# task_eagle.net
KiCad netlist of a schematic drawn in EAGLE
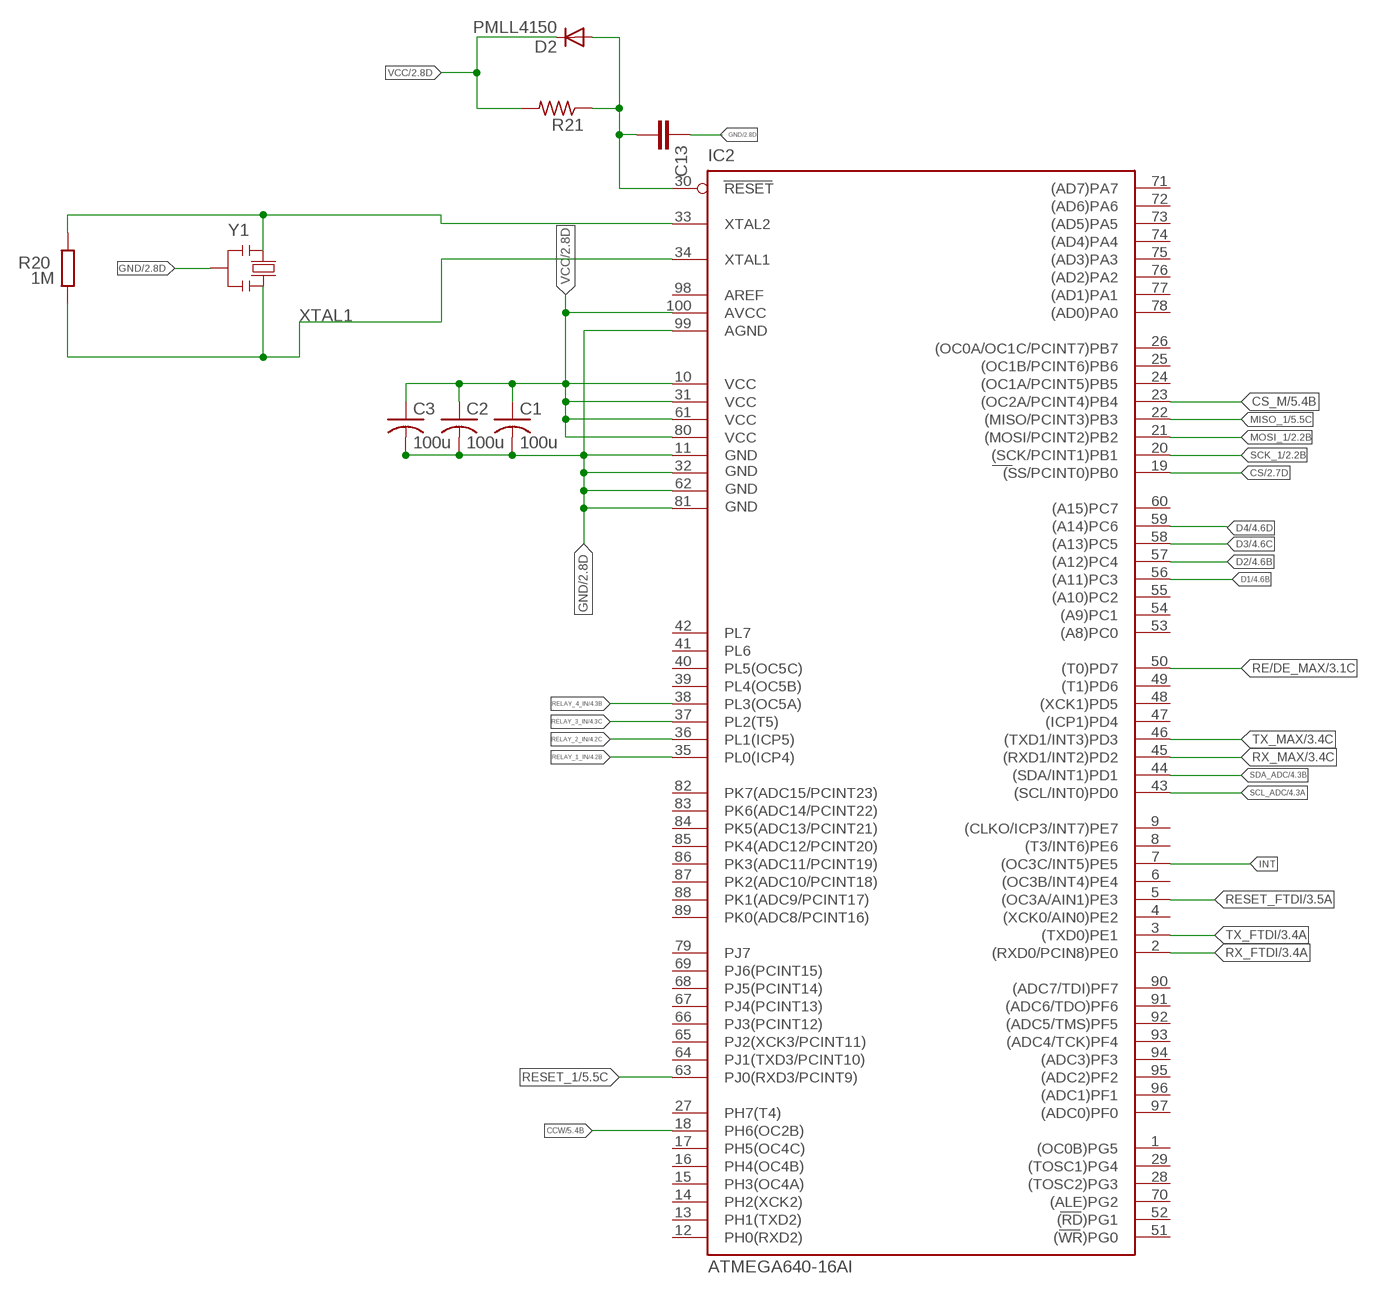
[diagram p0: schematic, sheet 1]
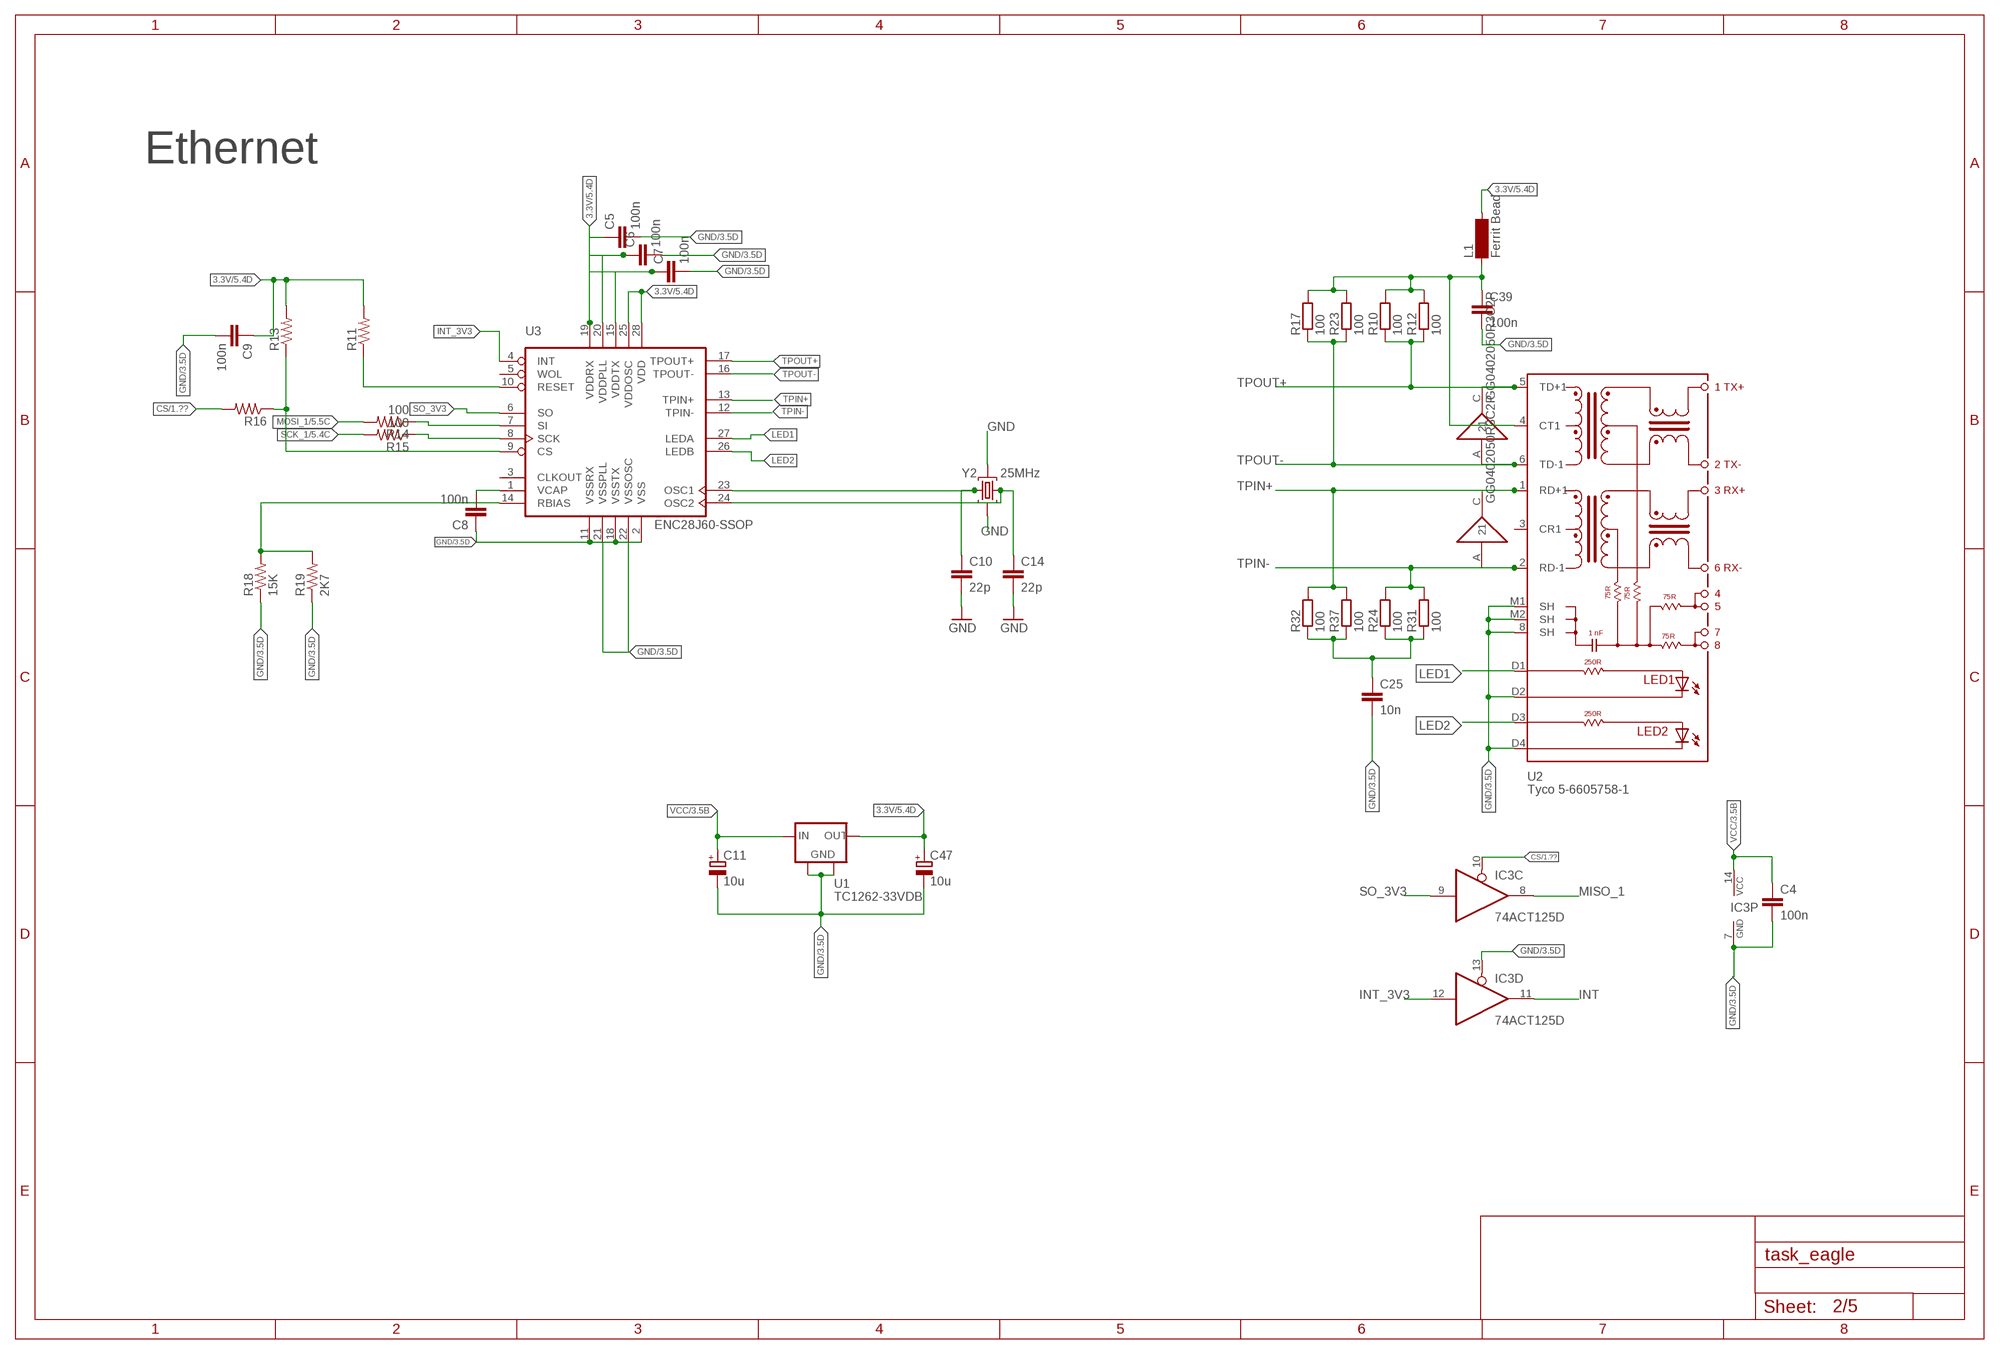
[diagram p1: schematic, sheet 2]
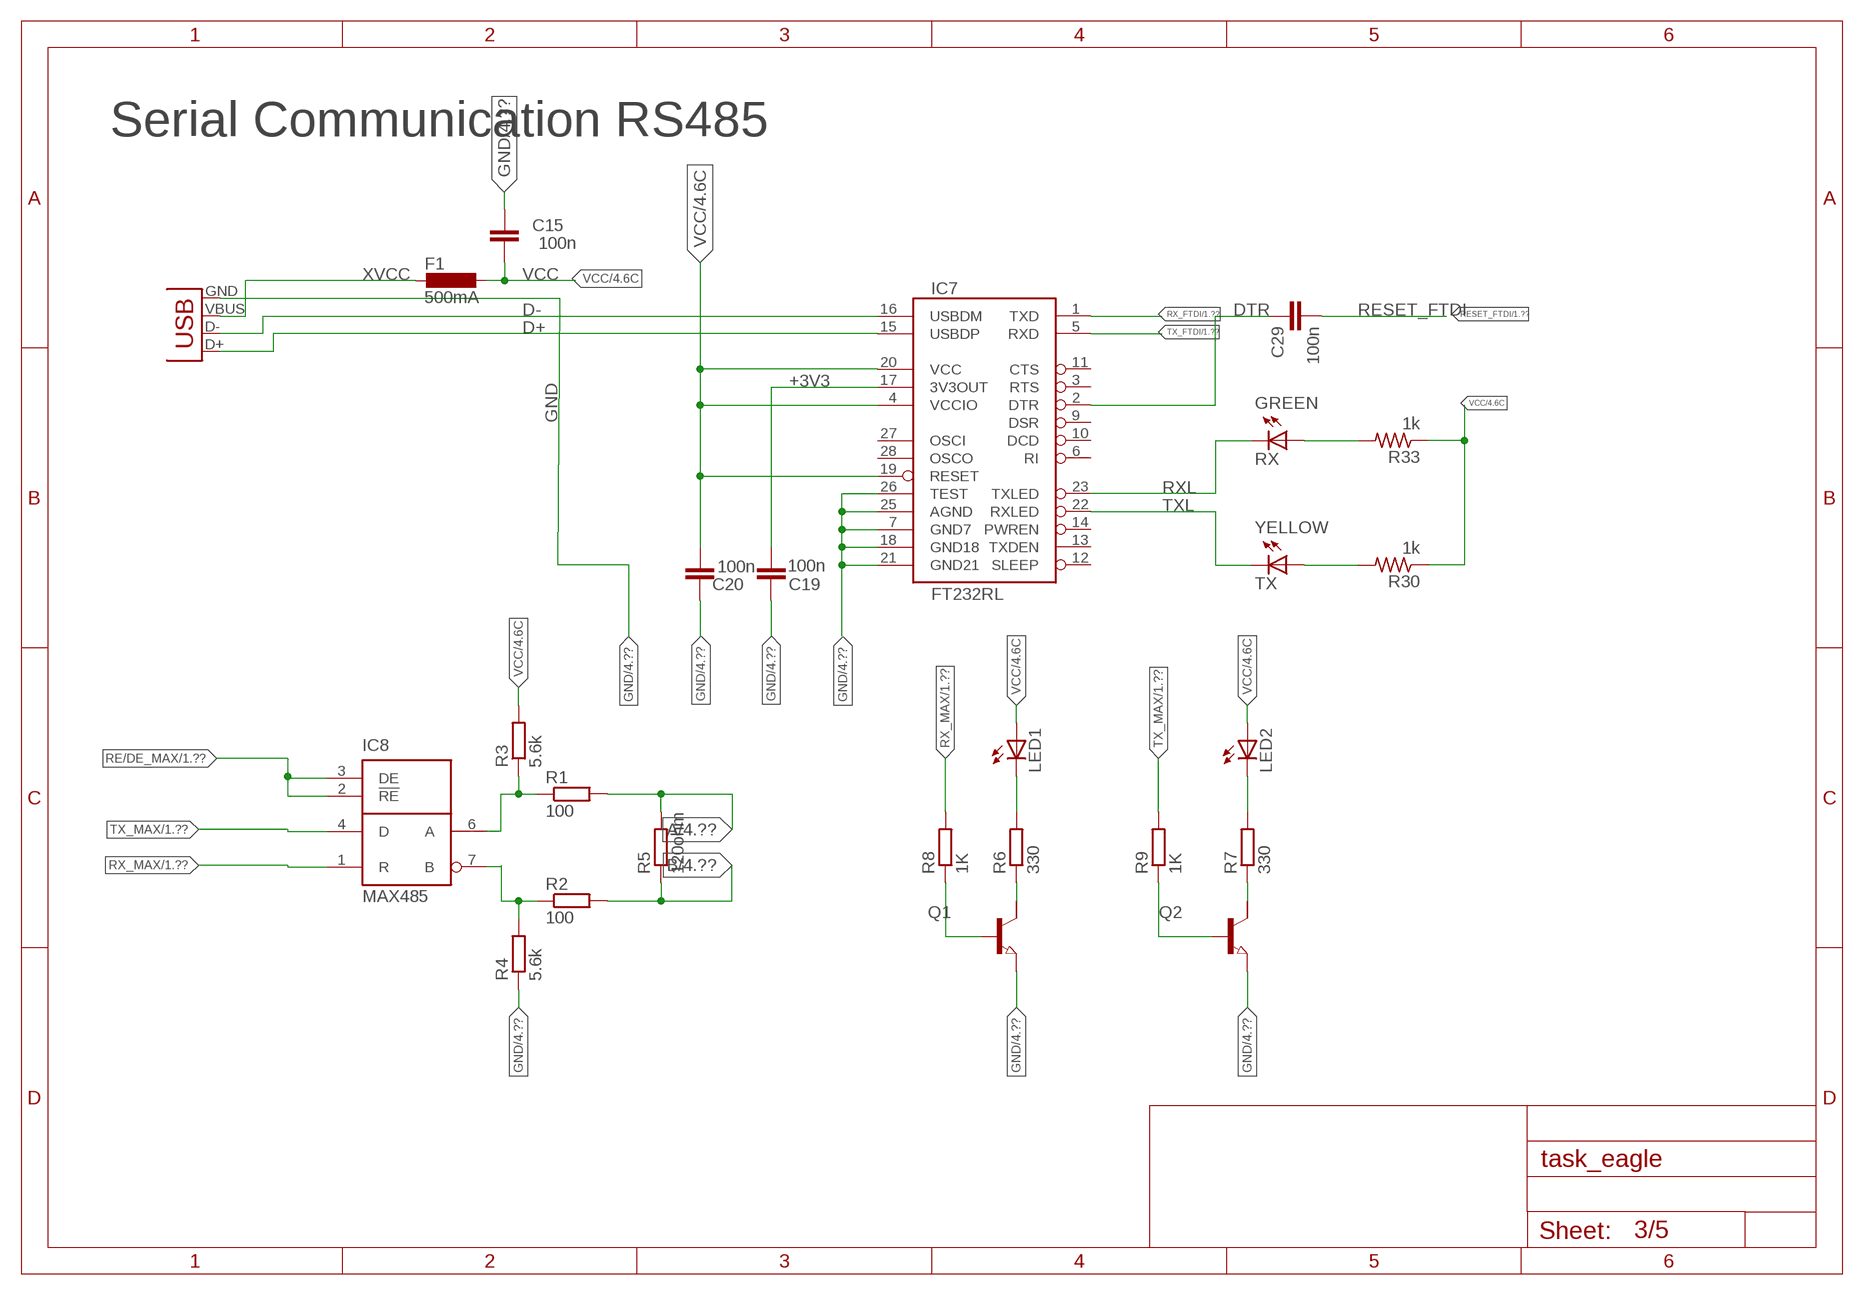
[diagram p2: schematic, sheet 3]
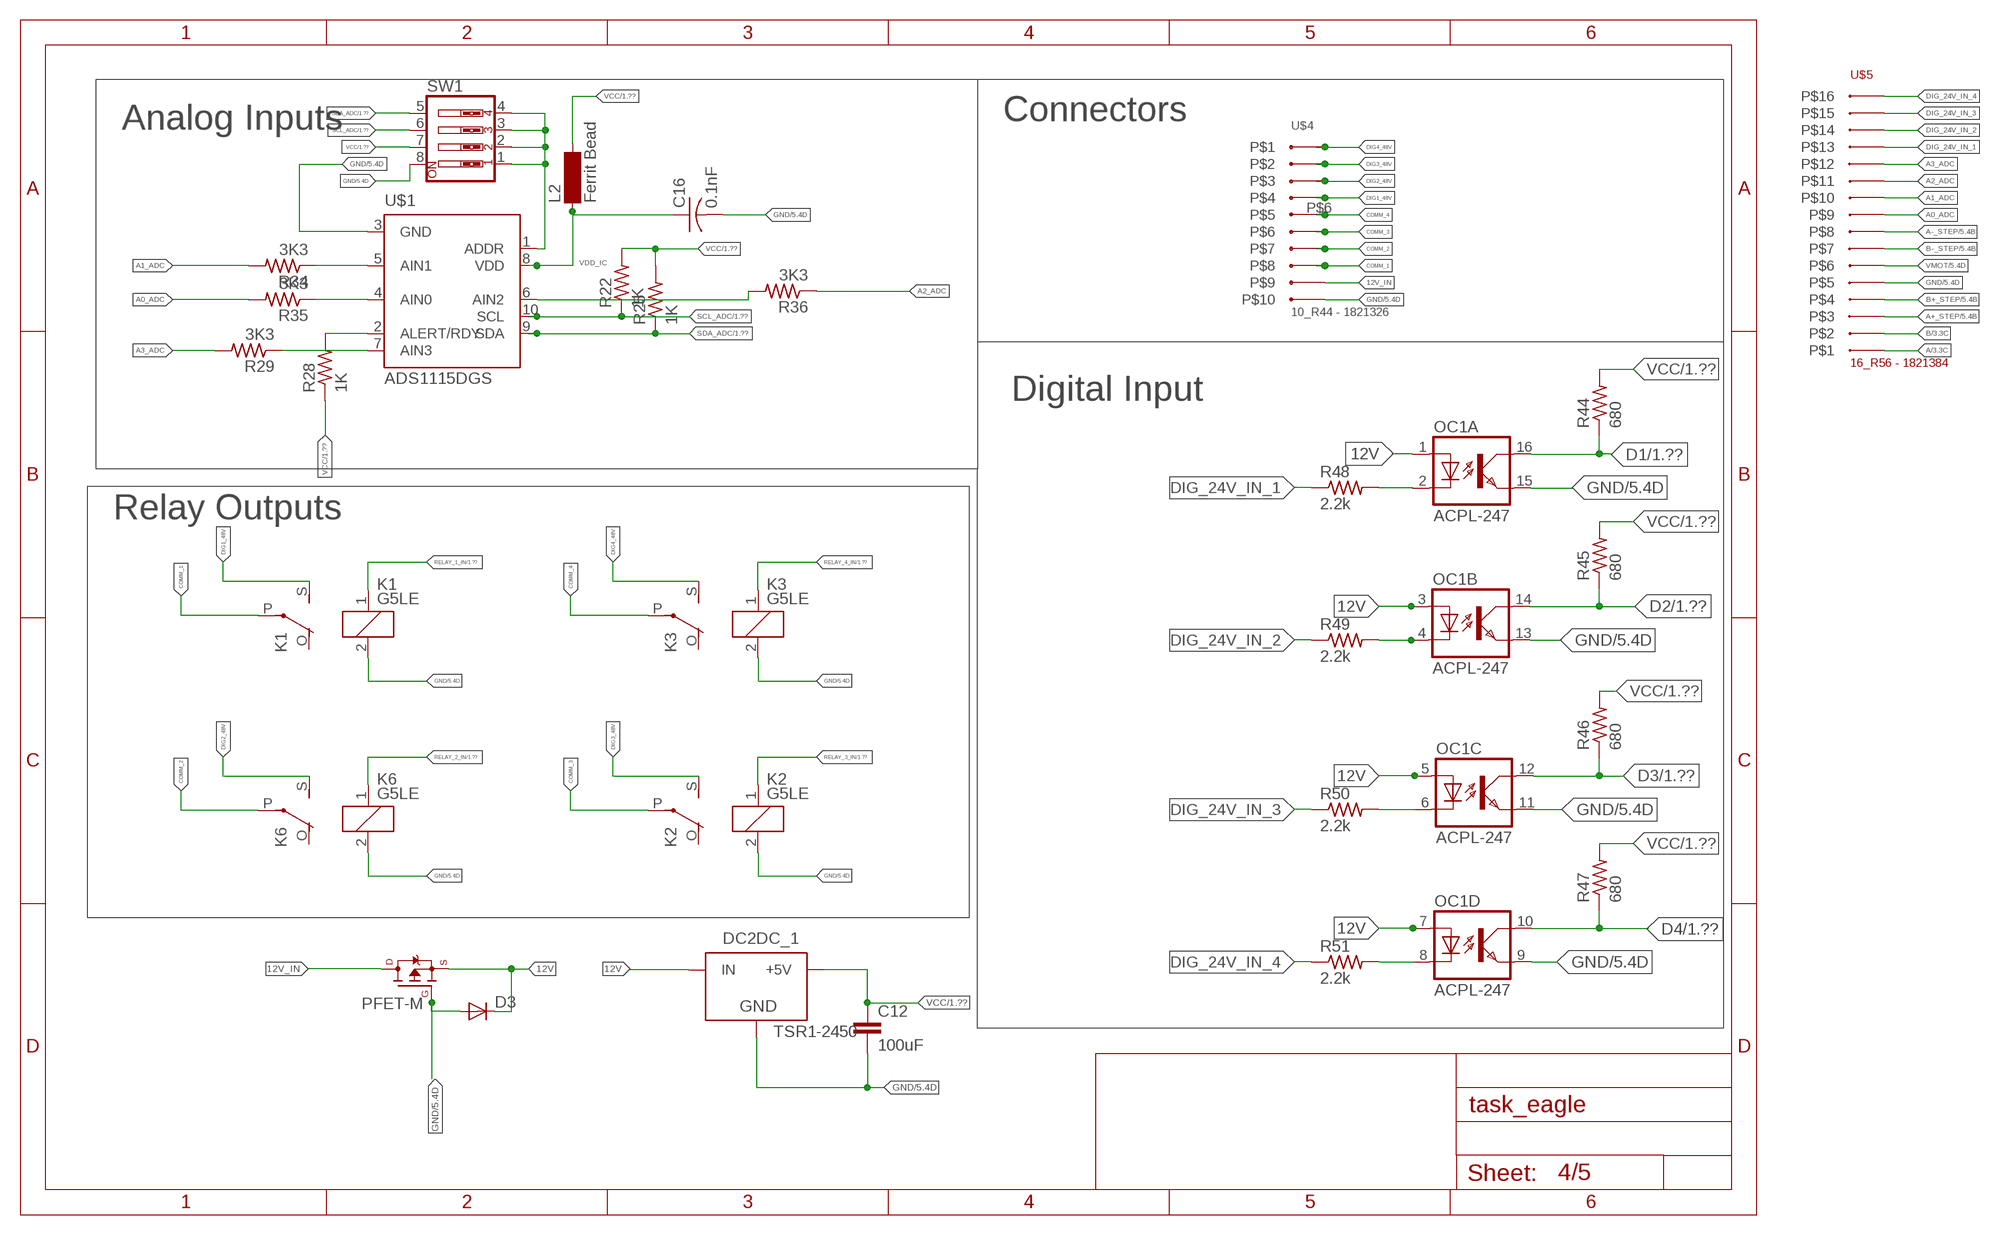
[diagram p3: schematic, sheet 4]
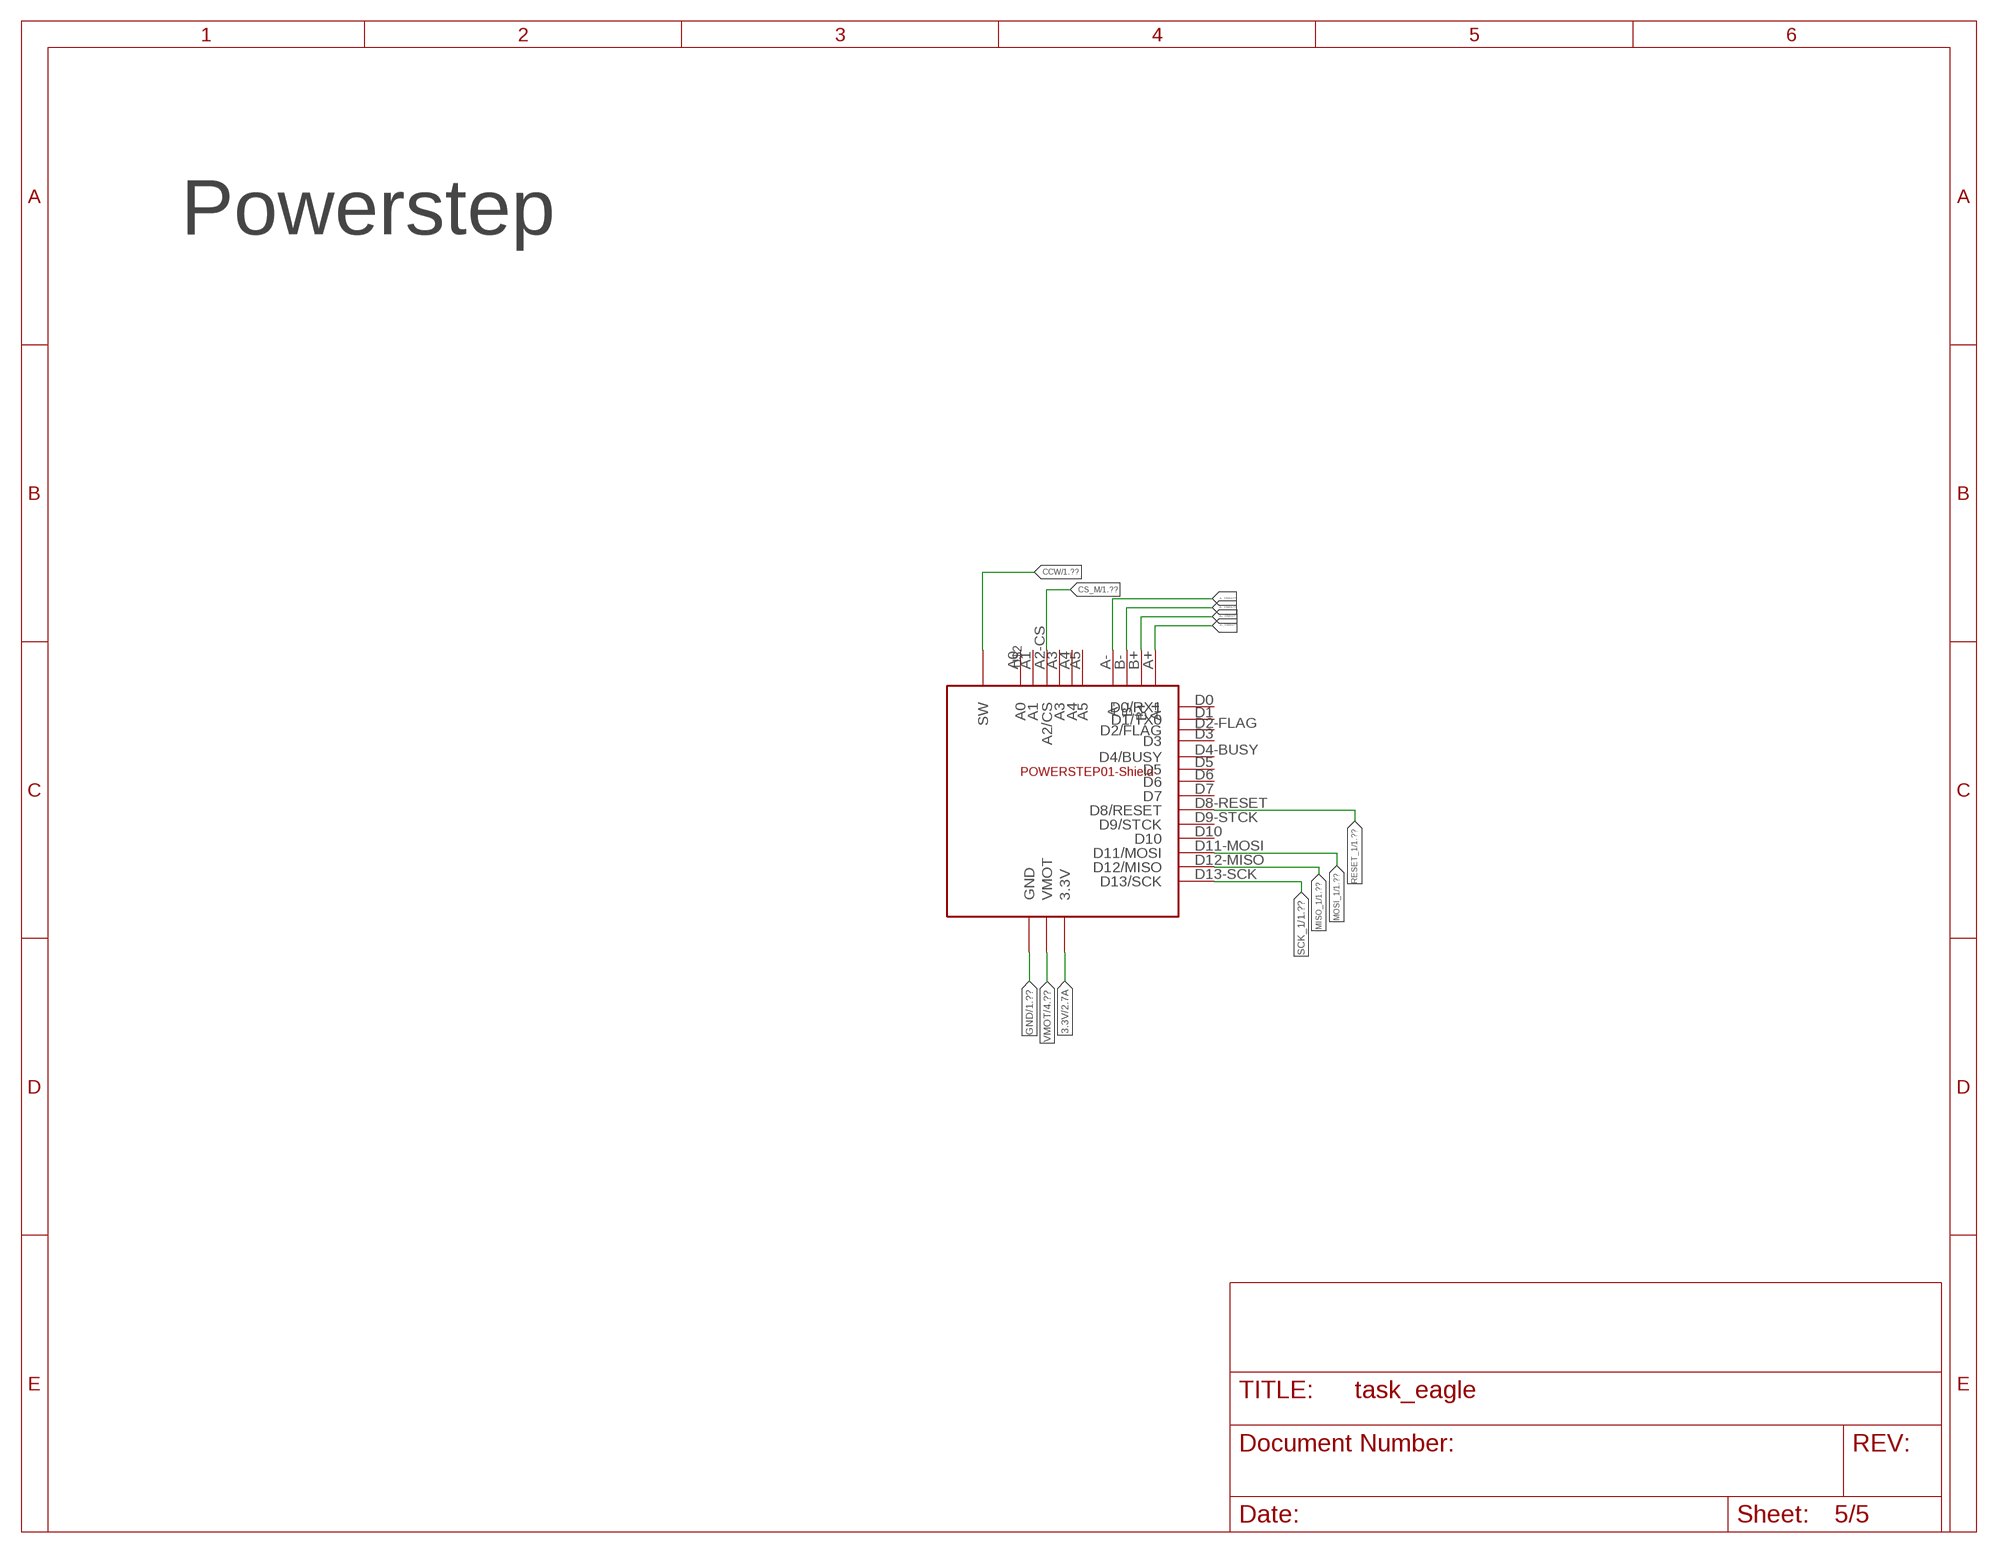
[diagram p4: schematic, sheet 5]

(export (version "E")
  (design (tool "Eeschema 10.0.6"))
  (components
    (comp (ref "C4")
      (value "100n")
      (footprint "eagle-import:C0603")
      (libsource (lib "eagle-import") (part "rcl_C-EUC0603"))
    )
    (comp (ref "C5")
      (value "100n")
      (footprint "eagle-import:C0603")
      (libsource (lib "eagle-import") (part "rcl_C-EUC0603"))
    )
    (comp (ref "C6")
      (value "100n")
      (footprint "eagle-import:C0603")
      (libsource (lib "eagle-import") (part "rcl_C-EUC0603"))
    )
    (comp (ref "C7")
      (value "100n")
      (footprint "eagle-import:C0603")
      (libsource (lib "eagle-import") (part "rcl_C-EUC0603"))
    )
    (comp (ref "C8")
      (value "100n")
      (footprint "eagle-import:C0603")
      (libsource (lib "eagle-import") (part "rcl_C-EUC0603"))
    )
    (comp (ref "C9")
      (value "100n")
      (footprint "eagle-import:C0603")
      (libsource (lib "eagle-import") (part "rcl_C-EUC0603"))
    )
    (comp (ref "C10")
      (value "22p")
      (footprint "eagle-import:C0603")
      (libsource (lib "eagle-import") (part "rcl_C-EUC0603"))
    )
    (comp (ref "C11")
      (value "10u")
      (footprint "eagle-import:153CLV-0605")
      (libsource (lib "eagle-import") (part "CPOL-EU153CLV-0605"))
    )
    (comp (ref "C14")
      (value "22p")
      (footprint "eagle-import:C0603")
      (libsource (lib "eagle-import") (part "rcl_C-EUC0603"))
    )
    (comp (ref "C25")
      (value "10n")
      (footprint "eagle-import:C0603")
      (libsource (lib "eagle-import") (part "rcl_C-EUC0603"))
    )
    (comp (ref "C39")
      (value "100n")
      (footprint "eagle-import:C0603")
      (libsource (lib "eagle-import") (part "rcl_C-EUC0603"))
    )
    (comp (ref "C47")
      (value "10u")
      (footprint "eagle-import:153CLV-0605")
      (libsource (lib "eagle-import") (part "CPOL-EU153CLV-0605"))
    )
    (comp (ref "IC3")
      (value "74ACT125D")
      (footprint "eagle-import:SO14")
      (libsource (lib "eagle-import") (part "74125DACT"))
    )
    (comp (ref "L1")
      (value "Ferrit Bead")
      (footprint "eagle-import:SM-1206")
      (libsource (lib "eagle-import") (part "SM-1206"))
    )
    (comp (ref "R10")
      (value "100")
      (footprint "eagle-import:R0603")
      (libsource (lib "eagle-import") (part "rcl_R-EU_R0603"))
    )
    (comp (ref "R11")
      (value "R-US_R0603")
      (footprint "eagle-import:R0603")
      (libsource (lib "eagle-import") (part "R-US_R0603"))
    )
    (comp (ref "R12")
      (value "100")
      (footprint "eagle-import:R0603")
      (libsource (lib "eagle-import") (part "rcl_R-EU_R0603"))
    )
    (comp (ref "R13")
      (value "R-US_R0603")
      (footprint "eagle-import:R0603")
      (libsource (lib "eagle-import") (part "R-US_R0603"))
    )
    (comp (ref "R14")
      (value "100")
      (footprint "eagle-import:R0603")
      (libsource (lib "eagle-import") (part "R-US_R0603"))
    )
    (comp (ref "R15")
      (value "100")
      (footprint "eagle-import:R0603")
      (libsource (lib "eagle-import") (part "R-US_R0603"))
    )
    (comp (ref "R16")
      (value "R-US_R0603")
      (footprint "eagle-import:R0603")
      (libsource (lib "eagle-import") (part "R-US_R0603"))
    )
    (comp (ref "R17")
      (value "100")
      (footprint "eagle-import:R0603")
      (libsource (lib "eagle-import") (part "rcl_R-EU_R0603"))
    )
    (comp (ref "R18")
      (value "15K")
      (footprint "eagle-import:R0603")
      (libsource (lib "eagle-import") (part "R-US_R0603"))
    )
    (comp (ref "R19")
      (value "2K7")
      (footprint "eagle-import:R0603")
      (libsource (lib "eagle-import") (part "R-US_R0603"))
    )
    (comp (ref "R23")
      (value "100")
      (footprint "eagle-import:R0603")
      (libsource (lib "eagle-import") (part "rcl_R-EU_R0603"))
    )
    (comp (ref "R24")
      (value "100")
      (footprint "eagle-import:R0603")
      (libsource (lib "eagle-import") (part "rcl_R-EU_R0603"))
    )
    (comp (ref "R31")
      (value "100")
      (footprint "eagle-import:R0603")
      (libsource (lib "eagle-import") (part "rcl_R-EU_R0603"))
    )
    (comp (ref "R32")
      (value "100")
      (footprint "eagle-import:R0603")
      (libsource (lib "eagle-import") (part "rcl_R-EU_R0603"))
    )
    (comp (ref "R37")
      (value "100")
      (footprint "eagle-import:R0603")
      (libsource (lib "eagle-import") (part "rcl_R-EU_R0603"))
    )
    (comp (ref "U$6")
      (value "GG0402050R3C2P")
      (footprint "eagle-import:0402")
      (libsource (lib "eagle-import") (part "GG0402050R3C2P"))
    )
    (comp (ref "U$7")
      (value "GG0402050R3C2P")
      (footprint "eagle-import:0402")
      (libsource (lib "eagle-import") (part "GG0402050R3C2P"))
    )
    (comp (ref "U1")
      (value "TC1262-33VDB")
      (footprint "eagle-import:SOT223")
      (libsource (lib "eagle-import") (part "TC1262-50VDB"))
    )
    (comp (ref "U2")
      (value "Tyco 5-6605758-1")
      (footprint "eagle-import:5-6605758-1")
      (libsource (lib "eagle-import") (part "5-6605758-1"))
    )
    (comp (ref "U3")
      (value "ENC28J60-SSOP")
      (footprint "eagle-import:SSOP28")
      (libsource (lib "eagle-import") (part "ENC28J60-SSOP"))
    )
    (comp (ref "Y2")
      (value "25MHz")
      (footprint "eagle-import:CRYSTAL-3.2-2.5")
      (libsource (lib "eagle-import") (part "CRYSTAL-3.2-2.5"))
    )
    (comp (ref "U$2")
      (value "POWERSTEP01-SHIELD")
      (footprint "eagle-import:POWERSTEP1")
      (libsource (lib "eagle-import") (part "POWERSTEP01-SHIELD"))
    )
    (comp (ref "C12")
      (value "100uF")
      (footprint "eagle-import:C0603")
      (libsource (lib "eagle-import") (part "CC0603"))
    )
    (comp (ref "C16")
      (value "0.1nF")
      (footprint "eagle-import:C0603")
      (libsource (lib "eagle-import") (part "C-USC0603"))
    )
    (comp (ref "D3")
      (value "DIODE-MINIMELF")
      (footprint "eagle-import:MINIMELF")
      (libsource (lib "eagle-import") (part "DIODE-MINIMELF"))
    )
    (comp (ref "DC2DC_1")
      (value "TSR1-2450")
      (footprint "eagle-import:TSR-1")
      (libsource (lib "eagle-import") (part "TSR1-2450"))
    )
    (comp (ref "K1")
      (value "G5LE")
      (footprint "eagle-import:G5LE")
      (libsource (lib "eagle-import") (part "G5LE"))
    )
    (comp (ref "K2")
      (value "G5LE")
      (footprint "eagle-import:G5LE")
      (libsource (lib "eagle-import") (part "G5LE"))
    )
    (comp (ref "K3")
      (value "G5LE")
      (footprint "eagle-import:G5LE")
      (libsource (lib "eagle-import") (part "G5LE"))
    )
    (comp (ref "K6")
      (value "G5LE")
      (footprint "eagle-import:G5LE")
      (libsource (lib "eagle-import") (part "G5LE"))
    )
    (comp (ref "L2")
      (value "Ferrit Bead")
      (footprint "eagle-import:SM-1206")
      (libsource (lib "eagle-import") (part "SM-1206"))
    )
    (comp (ref "OC1")
      (value "ACPL-247")
      (footprint "eagle-import:SOP16")
      (libsource (lib "eagle-import") (part "ACPL-247"))
    )
    (comp (ref "PFET-M")
      (value "FQP47P06NORMAL")
      (footprint "eagle-import:FQP47P06-NORMAL")
      (libsource (lib "eagle-import") (part "FQP47P06NORMAL"))
    )
    (comp (ref "R22")
      (value "1K")
      (footprint "eagle-import:R0603")
      (libsource (lib "eagle-import") (part "resistor_R-US_R0603"))
    )
    (comp (ref "R25")
      (value "1K")
      (footprint "eagle-import:R0603")
      (libsource (lib "eagle-import") (part "resistor_R-US_R0603"))
    )
    (comp (ref "R28")
      (value "1K")
      (footprint "eagle-import:R0603")
      (libsource (lib "eagle-import") (part "resistor_R-US_R0603"))
    )
    (comp (ref "R29")
      (value "3K3")
      (footprint "eagle-import:R0603")
      (libsource (lib "eagle-import") (part "resistor_R-US_R0603"))
    )
    (comp (ref "R34")
      (value "3K3")
      (footprint "eagle-import:R0603")
      (libsource (lib "eagle-import") (part "resistor_R-US_R0603"))
    )
    (comp (ref "R35")
      (value "3K3")
      (footprint "eagle-import:R0603")
      (libsource (lib "eagle-import") (part "resistor_R-US_R0603"))
    )
    (comp (ref "R36")
      (value "3K3")
      (footprint "eagle-import:R0603")
      (libsource (lib "eagle-import") (part "resistor_R-US_R0603"))
    )
    (comp (ref "R44")
      (value "680")
      (footprint "eagle-import:R0603")
      (libsource (lib "eagle-import") (part "R-US_R0603"))
    )
    (comp (ref "R45")
      (value "680")
      (footprint "eagle-import:R0603")
      (libsource (lib "eagle-import") (part "R-US_R0603"))
    )
    (comp (ref "R46")
      (value "680")
      (footprint "eagle-import:R0603")
      (libsource (lib "eagle-import") (part "R-US_R0603"))
    )
    (comp (ref "R47")
      (value "680")
      (footprint "eagle-import:R0603")
      (libsource (lib "eagle-import") (part "R-US_R0603"))
    )
    (comp (ref "R48")
      (value "2.2k")
      (footprint "eagle-import:R0603")
      (libsource (lib "eagle-import") (part "R-US_R0603"))
    )
    (comp (ref "R49")
      (value "2.2k")
      (footprint "eagle-import:R0603")
      (libsource (lib "eagle-import") (part "R-US_R0603"))
    )
    (comp (ref "R50")
      (value "2.2k")
      (footprint "eagle-import:R0603")
      (libsource (lib "eagle-import") (part "R-US_R0603"))
    )
    (comp (ref "R51")
      (value "2.2k")
      (footprint "eagle-import:R0603")
      (libsource (lib "eagle-import") (part "R-US_R0603"))
    )
    (comp (ref "SW1")
      (value "SW_DIP-4")
      (footprint "eagle-import:EDG-04")
      (libsource (lib "eagle-import") (part "SW_DIP-4"))
    )
    (comp (ref "U$1")
      (value "ADS1115DGS")
      (footprint "eagle-import:MSOP10")
      (libsource (lib "eagle-import") (part "ADS1115DGS"))
    )
    (comp (ref "U$4")
      (value "10_R44 - 1821326")
      (footprint "eagle-import:10_R44 - 1821326")
      (libsource (lib "eagle-import") (part "10_R44 - 1821326"))
    )
    (comp (ref "U$5")
      (value "16_R56 - 1821384")
      (footprint "eagle-import:16_R56 - 1821384")
      (libsource (lib "eagle-import") (part "16_R56 - 1821384"))
    )
    (comp (ref "C15")
      (value "100n")
      (footprint "eagle-import:C0603")
      (libsource (lib "eagle-import") (part "rcl_C-EUC0603"))
    )
    (comp (ref "C19")
      (value "100n")
      (footprint "eagle-import:C0603-ROUND")
      (libsource (lib "eagle-import") (part "C-EU0603-RND"))
    )
    (comp (ref "C20")
      (value "100n")
      (footprint "eagle-import:C0603-ROUND")
      (libsource (lib "eagle-import") (part "C-EU0603-RND"))
    )
    (comp (ref "C29")
      (value "100n")
      (footprint "eagle-import:C0603-ROUND")
      (libsource (lib "eagle-import") (part "C-EU0603-RND"))
    )
    (comp (ref "F1")
      (value "500mA")
      (footprint "eagle-import:L1812")
      (libsource (lib "eagle-import") (part "L-EUL1812"))
    )
    (comp (ref "IC7")
      (value "FT232RL")
      (footprint "eagle-import:SSOP28DB")
      (libsource (lib "eagle-import") (part "FT232RLSSOP"))
    )
    (comp (ref "IC8")
      (value "MAX485")
      (footprint "eagle-import:SO-08")
      (fields (field (name "MF") "TEXAS INSTRUMENTS") (field (name "MPN") "SN75ALS176AD"))
      (libsource (lib "eagle-import") (part "75ALS176DA"))
    )
    (comp (ref "LED1")
      (value "LED_ESML0603")
      (footprint "eagle-import:LED_SML0603")
      (libsource (lib "eagle-import") (part "LED_ESML0603"))
    )
    (comp (ref "LED2")
      (value "LED_ESML0603")
      (footprint "eagle-import:LED_SML0603")
      (libsource (lib "eagle-import") (part "LED_ESML0603"))
    )
    (comp (ref "Q1")
      (value "NPN-TRANSISTIOR-2COLSOT89")
      (footprint "eagle-import:SOT89")
      (libsource (lib "eagle-import") (part "NPN-TRANSISTIOR-2COLSOT89"))
    )
    (comp (ref "Q2")
      (value "NPN-TRANSISTIOR-2COLSOT89")
      (footprint "eagle-import:SOT89")
      (libsource (lib "eagle-import") (part "NPN-TRANSISTIOR-2COLSOT89"))
    )
    (comp (ref "R1")
      (value "100")
      (footprint "eagle-import:R0603")
      (libsource (lib "eagle-import") (part "RR0603"))
    )
    (comp (ref "R2")
      (value "100")
      (footprint "eagle-import:R0603")
      (libsource (lib "eagle-import") (part "RR0603"))
    )
    (comp (ref "R3")
      (value "5.6k")
      (footprint "eagle-import:R0603")
      (libsource (lib "eagle-import") (part "RR0603"))
    )
    (comp (ref "R4")
      (value "5.6k")
      (footprint "eagle-import:R0603")
      (libsource (lib "eagle-import") (part "RR0603"))
    )
    (comp (ref "R5")
      (value "120ohm")
      (footprint "eagle-import:R0603")
      (libsource (lib "eagle-import") (part "RR0603"))
    )
    (comp (ref "R6")
      (value "330")
      (footprint "eagle-import:R0603")
      (libsource (lib "eagle-import") (part "RR0603"))
    )
    (comp (ref "R7")
      (value "330")
      (footprint "eagle-import:R0603")
      (libsource (lib "eagle-import") (part "RR0603"))
    )
    (comp (ref "R8")
      (value "1K")
      (footprint "eagle-import:R0603")
      (libsource (lib "eagle-import") (part "RR0603"))
    )
    (comp (ref "R9")
      (value "1K")
      (footprint "eagle-import:R0603")
      (libsource (lib "eagle-import") (part "RR0603"))
    )
    (comp (ref "R30")
      (value "1k")
      (footprint "eagle-import:R0603")
      (libsource (lib "eagle-import") (part "resistor_R-US_R0603"))
    )
    (comp (ref "R33")
      (value "1k")
      (footprint "eagle-import:R0603")
      (libsource (lib "eagle-import") (part "resistor_R-US_R0603"))
    )
    (comp (ref "RX")
      (value "GREEN")
      (footprint "eagle-import:CHIPLED_0603")
      (libsource (lib "eagle-import") (part "LEDCHIPLED_0603"))
    )
    (comp (ref "TX")
      (value "YELLOW")
      (footprint "eagle-import:CHIPLED_0603")
      (libsource (lib "eagle-import") (part "LEDCHIPLED_0603"))
    )
    (comp (ref "USB")
      (value "USB")
      (footprint "eagle-import:USB-B-PTH-VERTICAL")
      (libsource (lib "eagle-import") (part "USBPTH-VERTICAL"))
    )
    (comp (ref "C1")
      (value "100u")
      (footprint "eagle-import:C0603")
      (libsource (lib "eagle-import") (part "C-USC0603"))
    )
    (comp (ref "C2")
      (value "100u")
      (footprint "eagle-import:C0603")
      (libsource (lib "eagle-import") (part "C-USC0603"))
    )
    (comp (ref "C3")
      (value "100u")
      (footprint "eagle-import:C0603")
      (libsource (lib "eagle-import") (part "C-USC0603"))
    )
    (comp (ref "C13")
      (value "CC0603")
      (footprint "eagle-import:C0603")
      (libsource (lib "eagle-import") (part "CC0603"))
    )
    (comp (ref "D2")
      (value "PMLL4150")
      (footprint "eagle-import:SOD80C")
      (libsource (lib "eagle-import") (part "PMLL4150"))
    )
    (comp (ref "IC2")
      (value "ATMEGA640-16AI")
      (footprint "eagle-import:TQFP100")
      (libsource (lib "eagle-import") (part "ATMEGAAI640-16"))
    )
    (comp (ref "R20")
      (value "1M")
      (footprint "eagle-import:R0603-ROUND")
      (libsource (lib "eagle-import") (part "R-EU_R0603"))
    )
    (comp (ref "R21")
      (value "R-US_R0603")
      (footprint "eagle-import:R0603")
      (libsource (lib "eagle-import") (part "resistor_R-US_R0603"))
    )
    (comp (ref "Y1")
      (value "RESONATORMU")
      (footprint "eagle-import:RESONATOR")
      (libsource (lib "eagle-import") (part "RESONATORMU"))
    )
  )
  (nets
    (net (code "1") (name "+3V3") (class "Default")
      (node (ref "C19") (pin "2") (pinfunction "2_2") (pintype "passive"))
      (node (ref "IC7") (pin "17") (pinfunction "3V3OUT_17") (pintype "output"))
    )
    (net (code "2") (name "3.3V") (class "Default")
      (node (ref "C47") (pin "+") (pinfunction "+_+") (pintype "passive"))
      (node (ref "C5") (pin "1") (pinfunction "1_1") (pintype "passive"))
      (node (ref "C6") (pin "1") (pinfunction "1_1") (pintype "passive"))
      (node (ref "C7") (pin "1") (pinfunction "1_1") (pintype "passive"))
      (node (ref "C9") (pin "1") (pinfunction "1_1") (pintype "passive"))
      (node (ref "L1") (pin "2") (pinfunction "2_2") (pintype "passive"))
      (node (ref "R11") (pin "2") (pinfunction "2_2") (pintype "passive"))
      (node (ref "R13") (pin "2") (pinfunction "2_2") (pintype "passive"))
      (node (ref "U$2") (pin "3.3V") (pinfunction "3.3V_3.3V") (pintype "power_in"))
      (node (ref "U$2") (pin "IOREF") (pinfunction "3.3V_IOREF") (pintype "power_in"))
      (node (ref "U1") (pin "3") (pinfunction "OUT_3") (pintype "passive"))
      (node (ref "U3") (pin "15") (pinfunction "VDDTX_15") (pintype "power_in"))
      (node (ref "U3") (pin "19") (pinfunction "VDDRX_19") (pintype "power_in"))
      (node (ref "U3") (pin "20") (pinfunction "VDDPLL_20") (pintype "power_in"))
      (node (ref "U3") (pin "25") (pinfunction "VDDOSC_25") (pintype "power_in"))
      (node (ref "U3") (pin "28") (pinfunction "VDD_28") (pintype "power_in"))
    )
    (net (code "3") (name "12V") (class "Default")
      (node (ref "D3") (pin "C") (pinfunction "C_C") (pintype "passive"))
      (node (ref "DC2DC_1") (pin "1") (pinfunction "IN_1") (pintype "power_in"))
      (node (ref "OC1") (pin "1") (pinfunction "A_1") (pintype "passive"))
      (node (ref "OC1") (pin "3") (pinfunction "A_3") (pintype "passive"))
      (node (ref "OC1") (pin "5") (pinfunction "A_5") (pintype "passive"))
      (node (ref "OC1") (pin "7") (pinfunction "A_7") (pintype "passive"))
      (node (ref "PFET-M") (pin "3") (pinfunction "S_3") (pintype "passive"))
    )
    (net (code "4") (name "12V_IN") (class "Default")
      (node (ref "PFET-M") (pin "2") (pinfunction "D_2") (pintype "passive"))
      (node (ref "U$4") (pin "P$10") (pinfunction "P$9_P$10") (pintype "bidirectional"))
    )
    (net (code "5") (name "A") (class "Default")
      (node (ref "R1") (pin "2") (pinfunction "2_2") (pintype "passive"))
      (node (ref "R5") (pin "2") (pinfunction "2_2") (pintype "passive"))
      (node (ref "U$5") (pin "P$1") (pinfunction "P$1_P$1") (pintype "bidirectional"))
    )
    (net (code "6") (name "A+_STEP") (class "Default")
      (node (ref "U$2") (pin "A+") (pinfunction "A+_A+") (pintype "bidirectional"))
      (node (ref "U$5") (pin "P$3") (pinfunction "P$3_P$3") (pintype "bidirectional"))
    )
    (net (code "7") (name "A-_STEP") (class "Default")
      (node (ref "U$2") (pin "A-") (pinfunction "A-_A-") (pintype "bidirectional"))
      (node (ref "U$5") (pin "P$8") (pinfunction "P$8_P$8") (pintype "bidirectional"))
    )
    (net (code "8") (name "A0_ADC") (class "Default")
      (node (ref "R35") (pin "2") (pinfunction "2_2") (pintype "passive"))
      (node (ref "U$5") (pin "P$9") (pinfunction "P$9_P$9") (pintype "bidirectional"))
    )
    (net (code "9") (name "A1_ADC") (class "Default")
      (node (ref "R34") (pin "2") (pinfunction "2_2") (pintype "passive"))
      (node (ref "U$5") (pin "P$10") (pinfunction "P$10_P$10") (pintype "bidirectional"))
    )
    (net (code "10") (name "A2_ADC") (class "Default")
      (node (ref "R36") (pin "1") (pinfunction "1_1") (pintype "passive"))
      (node (ref "U$5") (pin "P$11") (pinfunction "P$11_P$11") (pintype "bidirectional"))
    )
    (net (code "11") (name "A3_ADC") (class "Default")
      (node (ref "R29") (pin "2") (pinfunction "2_2") (pintype "passive"))
      (node (ref "U$5") (pin "P$12") (pinfunction "P$12_P$12") (pintype "bidirectional"))
    )
    (net (code "12") (name "B") (class "Default")
      (node (ref "R2") (pin "2") (pinfunction "2_2") (pintype "passive"))
      (node (ref "R5") (pin "1") (pinfunction "1_1") (pintype "passive"))
      (node (ref "U$5") (pin "P$2") (pinfunction "P$2_P$2") (pintype "bidirectional"))
    )
    (net (code "13") (name "B+_STEP") (class "Default")
      (node (ref "U$2") (pin "B+") (pinfunction "B+_B+") (pintype "bidirectional"))
      (node (ref "U$5") (pin "P$4") (pinfunction "P$4_P$4") (pintype "bidirectional"))
    )
    (net (code "14") (name "B-_STEP") (class "Default")
      (node (ref "U$2") (pin "B-") (pinfunction "B-_B-") (pintype "bidirectional"))
      (node (ref "U$5") (pin "P$7") (pinfunction "P$7_P$7") (pintype "bidirectional"))
    )
    (net (code "15") (name "CCW") (class "Default")
      (node (ref "IC2") (pin "18") (pinfunction "PH6(OC2B)_18") (pintype "bidirectional"))
      (node (ref "U$2") (pin "SW") (pinfunction "SW_SW") (pintype "input"))
    )
    (net (code "16") (name "COMM_1") (class "Default")
      (node (ref "K1") (pin "P") (pinfunction "P_P") (pintype "passive"))
      (node (ref "U$4") (pin "P$9") (pinfunction "P$8_P$9") (pintype "bidirectional"))
    )
    (net (code "17") (name "COMM_2") (class "Default")
      (node (ref "K6") (pin "P") (pinfunction "P_P") (pintype "passive"))
      (node (ref "U$4") (pin "P$8") (pinfunction "P$7_P$8") (pintype "bidirectional"))
    )
    (net (code "18") (name "COMM_3") (class "Default")
      (node (ref "K2") (pin "P") (pinfunction "P_P") (pintype "passive"))
      (node (ref "U$4") (pin "P$7") (pinfunction "P$6_P$7") (pintype "bidirectional"))
    )
    (net (code "19") (name "COMM_4") (class "Default")
      (node (ref "K3") (pin "P") (pinfunction "P_P") (pintype "passive"))
      (node (ref "U$4") (pin "P$6") (pinfunction "P$5_P$6") (pintype "bidirectional"))
    )
    (net (code "20") (name "CS") (class "Default")
      (node (ref "IC2") (pin "19") (pinfunction "(SS/PCINT0)PB0_19") (pintype "bidirectional"))
      (node (ref "IC3") (pin "10") (pinfunction "OE_10") (pintype "input"))
      (node (ref "R16") (pin "2") (pinfunction "2_2") (pintype "passive"))
    )
    (net (code "21") (name "CS_M") (class "Default")
      (node (ref "IC2") (pin "23") (pinfunction "(OC2A/PCINT4)PB4_23") (pintype "bidirectional"))
      (node (ref "U$2") (pin "A2-CS") (pinfunction "A2/CS_A2-CS") (pintype "bidirectional"))
    )
    (net (code "22") (name "D+") (class "Default")
      (node (ref "IC7") (pin "15") (pinfunction "USBDP_15") (pintype "bidirectional"))
      (node (ref "USB") (pin "D+") (pinfunction "D+_D+") (pintype "bidirectional"))
    )
    (net (code "23") (name "D-") (class "Default")
      (node (ref "IC7") (pin "16") (pinfunction "USBDM_16") (pintype "bidirectional"))
      (node (ref "USB") (pin "D-") (pinfunction "D-_D-") (pintype "bidirectional"))
    )
    (net (code "24") (name "D1") (class "Default")
      (node (ref "IC2") (pin "56") (pinfunction "(A11)PC3_56") (pintype "bidirectional"))
      (node (ref "OC1") (pin "16") (pinfunction "COL_16") (pintype "passive"))
      (node (ref "R44") (pin "1") (pinfunction "1_1") (pintype "passive"))
    )
    (net (code "25") (name "D2") (class "Default")
      (node (ref "IC2") (pin "57") (pinfunction "(A12)PC4_57") (pintype "bidirectional"))
      (node (ref "OC1") (pin "14") (pinfunction "COL_14") (pintype "passive"))
      (node (ref "R45") (pin "1") (pinfunction "1_1") (pintype "passive"))
    )
    (net (code "26") (name "D3") (class "Default")
      (node (ref "IC2") (pin "58") (pinfunction "(A13)PC5_58") (pintype "bidirectional"))
      (node (ref "OC1") (pin "12") (pinfunction "COL_12") (pintype "passive"))
      (node (ref "R46") (pin "1") (pinfunction "1_1") (pintype "passive"))
    )
    (net (code "27") (name "D4") (class "Default")
      (node (ref "IC2") (pin "59") (pinfunction "(A14)PC6_59") (pintype "bidirectional"))
      (node (ref "OC1") (pin "10") (pinfunction "COL_10") (pintype "passive"))
      (node (ref "R47") (pin "1") (pinfunction "1_1") (pintype "passive"))
    )
    (net (code "28") (name "DIG1_48V") (class "Default")
      (node (ref "K1") (pin "S") (pinfunction "S_S") (pintype "passive"))
      (node (ref "U$4") (pin "P$5") (pinfunction "P$4_P$5") (pintype "bidirectional"))
    )
    (net (code "29") (name "DIG2_48V") (class "Default")
      (node (ref "K6") (pin "S") (pinfunction "S_S") (pintype "passive"))
      (node (ref "U$4") (pin "P$4") (pinfunction "P$3_P$4") (pintype "bidirectional"))
    )
    (net (code "30") (name "DIG3_48V") (class "Default")
      (node (ref "K2") (pin "S") (pinfunction "S_S") (pintype "passive"))
      (node (ref "U$4") (pin "P$3") (pinfunction "P$2_P$3") (pintype "bidirectional"))
    )
    (net (code "31") (name "DIG4_48V") (class "Default")
      (node (ref "K3") (pin "S") (pinfunction "S_S") (pintype "passive"))
      (node (ref "U$4") (pin "P$2") (pinfunction "P$1_P$2") (pintype "bidirectional"))
    )
    (net (code "32") (name "DIG_24V_IN_1") (class "Default")
      (node (ref "R48") (pin "1") (pinfunction "1_1") (pintype "passive"))
      (node (ref "U$5") (pin "P$13") (pinfunction "P$13_P$13") (pintype "bidirectional"))
    )
    (net (code "33") (name "DIG_24V_IN_2") (class "Default")
      (node (ref "R49") (pin "1") (pinfunction "1_1") (pintype "passive"))
      (node (ref "U$5") (pin "P$14") (pinfunction "P$14_P$14") (pintype "bidirectional"))
    )
    (net (code "34") (name "DIG_24V_IN_3") (class "Default")
      (node (ref "R50") (pin "1") (pinfunction "1_1") (pintype "passive"))
      (node (ref "U$5") (pin "P$15") (pinfunction "P$15_P$15") (pintype "bidirectional"))
    )
    (net (code "35") (name "DIG_24V_IN_4") (class "Default")
      (node (ref "R51") (pin "1") (pinfunction "1_1") (pintype "passive"))
      (node (ref "U$5") (pin "P$16") (pinfunction "P$16_P$16") (pintype "bidirectional"))
    )
    (net (code "36") (name "DTR") (class "Default")
      (node (ref "C29") (pin "1") (pinfunction "1_1") (pintype "passive"))
      (node (ref "IC7") (pin "2") (pinfunction "DTR_2") (pintype "output"))
    )
    (net (code "37") (name "GND") (class "Default")
      (node (ref "C1") (pin "2") (pinfunction "2_2") (pintype "passive"))
      (node (ref "C10") (pin "2") (pinfunction "2_2") (pintype "passive"))
      (node (ref "C11") (pin "-") (pinfunction "-_-") (pintype "passive"))
      (node (ref "C12") (pin "2") (pinfunction "2_2") (pintype "passive"))
      (node (ref "C13") (pin "1") (pinfunction "1_1") (pintype "passive"))
      (node (ref "C14") (pin "2") (pinfunction "2_2") (pintype "passive"))
      (node (ref "C15") (pin "2") (pinfunction "2_2") (pintype "passive"))
      (node (ref "C16") (pin "2") (pinfunction "2_2") (pintype "passive"))
      (node (ref "C19") (pin "1") (pinfunction "1_1") (pintype "passive"))
      (node (ref "C2") (pin "2") (pinfunction "2_2") (pintype "passive"))
      (node (ref "C20") (pin "2") (pinfunction "2_2") (pintype "passive"))
      (node (ref "C25") (pin "2") (pinfunction "2_2") (pintype "passive"))
      (node (ref "C3") (pin "2") (pinfunction "2_2") (pintype "passive"))
      (node (ref "C39") (pin "2") (pinfunction "2_2") (pintype "passive"))
      (node (ref "C4") (pin "2") (pinfunction "2_2") (pintype "passive"))
      (node (ref "C47") (pin "-") (pinfunction "-_-") (pintype "passive"))
      (node (ref "C5") (pin "2") (pinfunction "2_2") (pintype "passive"))
      (node (ref "C6") (pin "2") (pinfunction "2_2") (pintype "passive"))
      (node (ref "C7") (pin "2") (pinfunction "2_2") (pintype "passive"))
      (node (ref "C8") (pin "1") (pinfunction "1_1") (pintype "passive"))
      (node (ref "C9") (pin "2") (pinfunction "2_2") (pintype "passive"))
      (node (ref "D3") (pin "A") (pinfunction "A_A") (pintype "passive"))
      (node (ref "DC2DC_1") (pin "2") (pinfunction "GND_2") (pintype "power_in"))
      (node (ref "IC2") (pin "11") (pinfunction "GND_11") (pintype "power_in"))
      (node (ref "IC2") (pin "32") (pinfunction "GND1_32") (pintype "power_in"))
      (node (ref "IC2") (pin "62") (pinfunction "GND2_62") (pintype "power_in"))
      (node (ref "IC2") (pin "81") (pinfunction "GND3_81") (pintype "power_in"))
      (node (ref "IC2") (pin "99") (pinfunction "AGND_99") (pintype "power_in"))
      (node (ref "IC3") (pin "13") (pinfunction "OE_13") (pintype "input"))
      (node (ref "IC3") (pin "7") (pinfunction "GND_7") (pintype "power_in"))
      (node (ref "IC7") (pin "18") (pinfunction "GND18_18") (pintype "power_in"))
      (node (ref "IC7") (pin "21") (pinfunction "GND21_21") (pintype "power_in"))
      (node (ref "IC7") (pin "25") (pinfunction "AGND_25") (pintype "power_in"))
      (node (ref "IC7") (pin "26") (pinfunction "TEST_26") (pintype "input"))
      (node (ref "IC7") (pin "7") (pinfunction "GND7_7") (pintype "power_in"))
      (node (ref "K1") (pin "2") (pinfunction "2_2") (pintype "passive"))
      (node (ref "K2") (pin "2") (pinfunction "2_2") (pintype "passive"))
      (node (ref "K3") (pin "2") (pinfunction "2_2") (pintype "passive"))
      (node (ref "K6") (pin "2") (pinfunction "2_2") (pintype "passive"))
      (node (ref "OC1") (pin "11") (pinfunction "EMIT_11") (pintype "passive"))
      (node (ref "OC1") (pin "13") (pinfunction "EMIT_13") (pintype "passive"))
      (node (ref "OC1") (pin "15") (pinfunction "EMIT_15") (pintype "passive"))
      (node (ref "OC1") (pin "9") (pinfunction "EMIT_9") (pintype "passive"))
      (node (ref "PFET-M") (pin "1") (pinfunction "G_1") (pintype "passive"))
      (node (ref "Q1") (pin "3") (pinfunction "E_3") (pintype "passive"))
      (node (ref "Q2") (pin "3") (pinfunction "E_3") (pintype "passive"))
      (node (ref "R18") (pin "1") (pinfunction "1_1") (pintype "passive"))
      (node (ref "R19") (pin "1") (pinfunction "1_1") (pintype "passive"))
      (node (ref "R4") (pin "1") (pinfunction "1_1") (pintype "passive"))
      (node (ref "SW1") (pin "8") (pinfunction "8_8") (pintype "passive"))
      (node (ref "U$1") (pin "3") (pinfunction "GND_3") (pintype "power_in"))
      (node (ref "U$2") (pin "GND@0") (pinfunction "GND_GND@0") (pintype "power_in"))
      (node (ref "U$2") (pin "GND@1") (pinfunction "GND_GND@1") (pintype "power_in"))
      (node (ref "U$2") (pin "GND@2") (pinfunction "GND_GND@2") (pintype "power_in"))
      (node (ref "U$2") (pin "GND@3") (pinfunction "GND_GND@3") (pintype "power_in"))
      (node (ref "U$4") (pin "P$11") (pinfunction "P$10_P$11") (pintype "bidirectional"))
      (node (ref "U$5") (pin "P$5") (pinfunction "P$5_P$5") (pintype "bidirectional"))
      (node (ref "U1") (pin "2") (pinfunction "GND_2") (pintype "input"))
      (node (ref "U1") (pin "4") (pinfunction "GND_4") (pintype "input"))
      (node (ref "U2") (pin "8") (pinfunction "SH_8") (pintype "input"))
      (node (ref "U2") (pin "D2") (pinfunction "D2_D2") (pintype "input"))
      (node (ref "U2") (pin "D4") (pinfunction "D4_D4") (pintype "input"))
      (node (ref "U2") (pin "M1") (pinfunction "SH_M1") (pintype "input"))
      (node (ref "U2") (pin "M2") (pinfunction "SH_M2") (pintype "input"))
      (node (ref "U3") (pin "11") (pinfunction "VSSRX_11") (pintype "power_in"))
      (node (ref "U3") (pin "18") (pinfunction "VSSTX_18") (pintype "power_in"))
      (node (ref "U3") (pin "2") (pinfunction "VSS_2") (pintype "power_in"))
      (node (ref "U3") (pin "21") (pinfunction "VSSPLL_21") (pintype "power_in"))
      (node (ref "U3") (pin "22") (pinfunction "VSSOSC_22") (pintype "power_in"))
      (node (ref "USB") (pin "GND") (pinfunction "GND_GND") (pintype "bidirectional"))
      (node (ref "Y1") (pin "2") (pinfunction "2_2") (pintype "passive"))
      (node (ref "Y2") (pin "2") (pinfunction "GND_2") (pintype "passive"))
      (node (ref "Y2") (pin "4") (pinfunction "GND_4") (pintype "passive"))
    )
    (net (code "38") (name "INT") (class "Default")
      (node (ref "IC2") (pin "7") (pinfunction "(OC3C/INT5)PE5_7") (pintype "bidirectional"))
      (node (ref "IC3") (pin "11") (pinfunction "O_11") (pintype "tri_state"))
    )
    (net (code "39") (name "INT_3V3") (class "Default")
      (node (ref "IC3") (pin "12") (pinfunction "I_12") (pintype "input"))
      (node (ref "U3") (pin "4") (pinfunction "INT_4") (pintype "output"))
    )
    (net (code "40") (name "LED1") (class "Default")
      (node (ref "U2") (pin "D1") (pinfunction "D1_D1") (pintype "input"))
      (node (ref "U3") (pin "27") (pinfunction "LEDA_27") (pintype "output"))
    )
    (net (code "41") (name "LED2") (class "Default")
      (node (ref "U2") (pin "D3") (pinfunction "D3_D3") (pintype "input"))
      (node (ref "U3") (pin "26") (pinfunction "LEDB_26") (pintype "output"))
    )
    (net (code "42") (name "MISO_1") (class "Default")
      (node (ref "IC2") (pin "22") (pinfunction "(MISO/PCINT3)PB3_22") (pintype "bidirectional"))
      (node (ref "IC3") (pin "8") (pinfunction "O_8") (pintype "tri_state"))
      (node (ref "U$2") (pin "D12-MISO") (pinfunction "D12/MISO_D12-MISO") (pintype "bidirectional"))
    )
    (net (code "43") (name "MOSI_1") (class "Default")
      (node (ref "IC2") (pin "21") (pinfunction "(MOSI/PCINT2)PB2_21") (pintype "bidirectional"))
      (node (ref "R14") (pin "2") (pinfunction "2_2") (pintype "passive"))
      (node (ref "U$2") (pin "D11-MOSI") (pinfunction "D11/MOSI_D11-MOSI") (pintype "bidirectional"))
    )
    (net (code "44") (name "Net-(C25-Pad1)") (class "Default")
      (node (ref "C25") (pin "1") (pinfunction "1_1") (pintype "passive"))
      (node (ref "R24") (pin "1") (pinfunction "1_1") (pintype "passive"))
      (node (ref "R31") (pin "1") (pinfunction "1_1") (pintype "passive"))
      (node (ref "R32") (pin "1") (pinfunction "1_1") (pintype "passive"))
      (node (ref "R37") (pin "1") (pinfunction "1_1") (pintype "passive"))
    )
    (net (code "45") (name "Net-(IC2-RESET)") (class "Default")
      (node (ref "C13") (pin "2") (pinfunction "2_2") (pintype "passive"))
      (node (ref "D2") (pin "A") (pinfunction "A_A") (pintype "passive"))
      (node (ref "IC2") (pin "30") (pinfunction "RESET_30") (pintype "input"))
      (node (ref "R21") (pin "1") (pinfunction "1_1") (pintype "passive"))
    )
    (net (code "46") (name "Net-(IC2-XTAL2)") (class "Default")
      (node (ref "IC2") (pin "33") (pinfunction "XTAL2_33") (pintype "output"))
      (node (ref "R20") (pin "2") (pinfunction "2_2") (pintype "passive"))
      (node (ref "Y1") (pin "1") (pinfunction "1_1") (pintype "passive"))
    )
    (net (code "47") (name "Net-(IC8A-A)") (class "Default")
      (node (ref "IC8") (pin "6") (pinfunction "A_6") (pintype "bidirectional"))
      (node (ref "R1") (pin "1") (pinfunction "1_1") (pintype "passive"))
      (node (ref "R3") (pin "1") (pinfunction "1_1") (pintype "passive"))
    )
    (net (code "48") (name "Net-(IC8A-B)") (class "Default")
      (node (ref "IC8") (pin "7") (pinfunction "B_7") (pintype "bidirectional"))
      (node (ref "R2") (pin "1") (pinfunction "1_1") (pintype "passive"))
      (node (ref "R4") (pin "2") (pinfunction "2_2") (pintype "passive"))
    )
    (net (code "49") (name "Net-(LED1-PadC)") (class "Default")
      (node (ref "LED1") (pin "C") (pinfunction "C_C") (pintype "passive"))
      (node (ref "R6") (pin "2") (pinfunction "2_2") (pintype "passive"))
    )
    (net (code "50") (name "Net-(LED2-PadC)") (class "Default")
      (node (ref "LED2") (pin "C") (pinfunction "C_C") (pintype "passive"))
      (node (ref "R7") (pin "2") (pinfunction "2_2") (pintype "passive"))
    )
    (net (code "51") (name "Net-(OC1A-C)") (class "Default")
      (node (ref "OC1") (pin "2") (pinfunction "C_2") (pintype "passive"))
      (node (ref "R48") (pin "2") (pinfunction "2_2") (pintype "passive"))
    )
    (net (code "52") (name "Net-(OC1B-C)") (class "Default")
      (node (ref "OC1") (pin "4") (pinfunction "C_4") (pintype "passive"))
      (node (ref "R49") (pin "2") (pinfunction "2_2") (pintype "passive"))
    )
    (net (code "53") (name "Net-(OC1C-C)") (class "Default")
      (node (ref "OC1") (pin "6") (pinfunction "C_6") (pintype "passive"))
      (node (ref "R50") (pin "2") (pinfunction "2_2") (pintype "passive"))
    )
    (net (code "54") (name "Net-(OC1D-C)") (class "Default")
      (node (ref "OC1") (pin "8") (pinfunction "C_8") (pintype "passive"))
      (node (ref "R51") (pin "2") (pinfunction "2_2") (pintype "passive"))
    )
    (net (code "55") (name "Net-(Q1-B)") (class "Default")
      (node (ref "Q1") (pin "1") (pinfunction "B_1") (pintype "passive"))
      (node (ref "R8") (pin "1") (pinfunction "1_1") (pintype "passive"))
    )
    (net (code "56") (name "Net-(Q1-C)") (class "Default")
      (node (ref "Q1") (pin "2") (pinfunction "C_2") (pintype "passive"))
      (node (ref "R6") (pin "1") (pinfunction "1_1") (pintype "passive"))
    )
    (net (code "57") (name "Net-(Q2-B)") (class "Default")
      (node (ref "Q2") (pin "1") (pinfunction "B_1") (pintype "passive"))
      (node (ref "R9") (pin "1") (pinfunction "1_1") (pintype "passive"))
    )
    (net (code "58") (name "Net-(Q2-C)") (class "Default")
      (node (ref "Q2") (pin "2") (pinfunction "C_2") (pintype "passive"))
      (node (ref "R7") (pin "1") (pinfunction "1_1") (pintype "passive"))
    )
    (net (code "59") (name "Net-(R30-Pad2)") (class "Default")
      (node (ref "R30") (pin "2") (pinfunction "2_2") (pintype "passive"))
      (node (ref "TX") (pin "A") (pinfunction "A_A") (pintype "passive"))
    )
    (net (code "60") (name "Net-(R33-Pad2)") (class "Default")
      (node (ref "R33") (pin "2") (pinfunction "2_2") (pintype "passive"))
      (node (ref "RX") (pin "A") (pinfunction "A_A") (pintype "passive"))
    )
    (net (code "61") (name "Net-(U$1-ADDR)") (class "Default")
      (node (ref "SW1") (pin "1") (pinfunction "1_1") (pintype "passive"))
      (node (ref "SW1") (pin "2") (pinfunction "2_2") (pintype "passive"))
      (node (ref "SW1") (pin "3") (pinfunction "3_3") (pintype "passive"))
      (node (ref "SW1") (pin "4") (pinfunction "4_4") (pintype "passive"))
      (node (ref "U$1") (pin "1") (pinfunction "ADDR_1") (pintype "input"))
    )
    (net (code "62") (name "Net-(U$1-AIN0)") (class "Default")
      (node (ref "R35") (pin "1") (pinfunction "1_1") (pintype "passive"))
      (node (ref "U$1") (pin "4") (pinfunction "AIN0_4") (pintype "input"))
    )
    (net (code "63") (name "Net-(U$1-AIN1)") (class "Default")
      (node (ref "R34") (pin "1") (pinfunction "1_1") (pintype "passive"))
      (node (ref "U$1") (pin "5") (pinfunction "AIN1_5") (pintype "input"))
    )
    (net (code "64") (name "Net-(U$1-AIN2)") (class "Default")
      (node (ref "R36") (pin "2") (pinfunction "2_2") (pintype "passive"))
      (node (ref "U$1") (pin "6") (pinfunction "AIN2_6") (pintype "input"))
    )
    (net (code "65") (name "Net-(U$1-AIN3)") (class "Default")
      (node (ref "R29") (pin "1") (pinfunction "1_1") (pintype "passive"))
      (node (ref "U$1") (pin "7") (pinfunction "AIN3_7") (pintype "power_in"))
    )
    (net (code "66") (name "Net-(U$1-ALERT{slash}RDY)") (class "Default")
      (node (ref "R28") (pin "2") (pinfunction "2_2") (pintype "passive"))
      (node (ref "U$1") (pin "2") (pinfunction "ALERT/RDY_2") (pintype "power_in"))
    )
    (net (code "67") (name "Net-(U2-CT1)") (class "Default")
      (node (ref "C39") (pin "1") (pinfunction "1_1") (pintype "passive"))
      (node (ref "L1") (pin "1") (pinfunction "1_1") (pintype "passive"))
      (node (ref "R10") (pin "2") (pinfunction "2_2") (pintype "passive"))
      (node (ref "R12") (pin "2") (pinfunction "2_2") (pintype "passive"))
      (node (ref "R17") (pin "2") (pinfunction "2_2") (pintype "passive"))
      (node (ref "R23") (pin "2") (pinfunction "2_2") (pintype "passive"))
      (node (ref "U2") (pin "4") (pinfunction "CT1_4") (pintype "input"))
    )
    (net (code "68") (name "Net-(U3-CS)") (class "Default")
      (node (ref "R13") (pin "1") (pinfunction "1_1") (pintype "passive"))
      (node (ref "R16") (pin "1") (pinfunction "1_1") (pintype "passive"))
      (node (ref "U3") (pin "9") (pinfunction "CS_9") (pintype "input"))
    )
    (net (code "69") (name "Net-(U3-OSC1)") (class "Default")
      (node (ref "C10") (pin "1") (pinfunction "1_1") (pintype "passive"))
      (node (ref "U3") (pin "23") (pinfunction "OSC1_23") (pintype "input"))
      (node (ref "Y2") (pin "3") (pinfunction "C2_3") (pintype "passive"))
    )
    (net (code "70") (name "Net-(U3-OSC2)") (class "Default")
      (node (ref "C14") (pin "1") (pinfunction "1_1") (pintype "passive"))
      (node (ref "U3") (pin "24") (pinfunction "OSC2_24") (pintype "output"))
      (node (ref "Y2") (pin "1") (pinfunction "C1_1") (pintype "passive"))
    )
    (net (code "71") (name "Net-(U3-RBIAS)") (class "Default")
      (node (ref "R18") (pin "2") (pinfunction "2_2") (pintype "passive"))
      (node (ref "R19") (pin "2") (pinfunction "2_2") (pintype "passive"))
      (node (ref "U3") (pin "14") (pinfunction "RBIAS_14") (pintype "passive"))
    )
    (net (code "72") (name "Net-(U3-RESET)") (class "Default")
      (node (ref "R11") (pin "1") (pinfunction "1_1") (pintype "passive"))
      (node (ref "U3") (pin "10") (pinfunction "RESET_10") (pintype "input"))
    )
    (net (code "73") (name "Net-(U3-SCK)") (class "Default")
      (node (ref "R15") (pin "1") (pinfunction "1_1") (pintype "passive"))
      (node (ref "U3") (pin "8") (pinfunction "SCK_8") (pintype "input"))
    )
    (net (code "74") (name "Net-(U3-SI)") (class "Default")
      (node (ref "R14") (pin "1") (pinfunction "1_1") (pintype "passive"))
      (node (ref "U3") (pin "7") (pinfunction "SI_7") (pintype "input"))
    )
    (net (code "75") (name "Net-(U3-VCAP)") (class "Default")
      (node (ref "C8") (pin "2") (pinfunction "2_2") (pintype "passive"))
      (node (ref "U3") (pin "1") (pinfunction "VCAP_1") (pintype "power_in"))
    )
    (net (code "76") (name "RELAY_1_IN") (class "Default")
      (node (ref "IC2") (pin "35") (pinfunction "PL0(ICP4)_35") (pintype "bidirectional"))
      (node (ref "K1") (pin "1") (pinfunction "1_1") (pintype "passive"))
    )
    (net (code "77") (name "RELAY_2_IN") (class "Default")
      (node (ref "IC2") (pin "36") (pinfunction "PL1(ICP5)_36") (pintype "bidirectional"))
      (node (ref "K6") (pin "1") (pinfunction "1_1") (pintype "passive"))
    )
    (net (code "78") (name "RELAY_3_IN") (class "Default")
      (node (ref "IC2") (pin "37") (pinfunction "PL2(T5)_37") (pintype "bidirectional"))
      (node (ref "K2") (pin "1") (pinfunction "1_1") (pintype "passive"))
    )
    (net (code "79") (name "RELAY_4_IN") (class "Default")
      (node (ref "IC2") (pin "38") (pinfunction "PL3(OC5A)_38") (pintype "bidirectional"))
      (node (ref "K3") (pin "1") (pinfunction "1_1") (pintype "passive"))
    )
    (net (code "80") (name "RESET_1") (class "Default")
      (node (ref "IC2") (pin "63") (pinfunction "PJ0(RXD3/PCINT9)_63") (pintype "bidirectional"))
      (node (ref "U$2") (pin "D8-RESET") (pinfunction "D8/RESET_D8-RESET") (pintype "bidirectional"))
    )
    (net (code "81") (name "RESET_FTDI") (class "Default")
      (node (ref "C29") (pin "2") (pinfunction "2_2") (pintype "passive"))
      (node (ref "IC2") (pin "5") (pinfunction "(OC3A/AIN1)PE3_5") (pintype "bidirectional"))
    )
    (net (code "82") (name "RE{slash}DE_MAX") (class "Default")
      (node (ref "IC2") (pin "50") (pinfunction "(T0)PD7_50") (pintype "bidirectional"))
      (node (ref "IC8") (pin "2") (pinfunction "~{RE}_2") (pintype "input"))
      (node (ref "IC8") (pin "3") (pinfunction "DE_3") (pintype "input"))
    )
    (net (code "83") (name "RXL") (class "Default")
      (node (ref "IC7") (pin "23") (pinfunction "TXLED_23") (pintype "input"))
      (node (ref "RX") (pin "C") (pinfunction "C_C") (pintype "passive"))
    )
    (net (code "84") (name "RX_FTDI") (class "Default")
      (node (ref "IC2") (pin "2") (pinfunction "(RXD0/PCIN8)PE0_2") (pintype "bidirectional"))
      (node (ref "IC7") (pin "1") (pinfunction "TXD_1") (pintype "output"))
    )
    (net (code "85") (name "RX_MAX") (class "Default")
      (node (ref "IC2") (pin "45") (pinfunction "(RXD1/INT2)PD2_45") (pintype "bidirectional"))
      (node (ref "IC8") (pin "1") (pinfunction "R_1") (pintype "output"))
      (node (ref "R8") (pin "2") (pinfunction "2_2") (pintype "passive"))
    )
    (net (code "86") (name "SCK_1") (class "Default")
      (node (ref "IC2") (pin "20") (pinfunction "(SCK/PCINT1)PB1_20") (pintype "bidirectional"))
      (node (ref "R15") (pin "2") (pinfunction "2_2") (pintype "passive"))
      (node (ref "U$2") (pin "D13-SCK") (pinfunction "D13/SCK_D13-SCK") (pintype "bidirectional"))
    )
    (net (code "87") (name "SCL_ADC") (class "Default")
      (node (ref "IC2") (pin "43") (pinfunction "(SCL/INT0)PD0_43") (pintype "bidirectional"))
      (node (ref "R22") (pin "1") (pinfunction "1_1") (pintype "passive"))
      (node (ref "SW1") (pin "6") (pinfunction "6_6") (pintype "passive"))
      (node (ref "U$1") (pin "10") (pinfunction "SCL_10") (pintype "input"))
    )
    (net (code "88") (name "SDA_ADC") (class "Default")
      (node (ref "IC2") (pin "44") (pinfunction "(SDA/INT1)PD1_44") (pintype "bidirectional"))
      (node (ref "R25") (pin "1") (pinfunction "1_1") (pintype "passive"))
      (node (ref "SW1") (pin "5") (pinfunction "5_5") (pintype "passive"))
      (node (ref "U$1") (pin "9") (pinfunction "SDA_9") (pintype "bidirectional"))
    )
    (net (code "89") (name "SO_3V3") (class "Default")
      (node (ref "IC3") (pin "9") (pinfunction "I_9") (pintype "input"))
      (node (ref "U3") (pin "6") (pinfunction "SO_6") (pintype "output"))
    )
    (net (code "90") (name "TPIN+") (class "Default")
      (node (ref "R32") (pin "2") (pinfunction "2_2") (pintype "passive"))
      (node (ref "R37") (pin "2") (pinfunction "2_2") (pintype "passive"))
      (node (ref "U$7") (pin "C") (pinfunction "2_C") (pintype "bidirectional"))
      (node (ref "U2") (pin "1") (pinfunction "RD+1_1") (pintype "input"))
      (node (ref "U3") (pin "13") (pinfunction "TPIN+_13") (pintype "input"))
    )
    (net (code "91") (name "TPIN-") (class "Default")
      (node (ref "R24") (pin "2") (pinfunction "2_2") (pintype "passive"))
      (node (ref "R31") (pin "2") (pinfunction "2_2") (pintype "passive"))
      (node (ref "U$7") (pin "A") (pinfunction "1_A") (pintype "bidirectional"))
      (node (ref "U2") (pin "2") (pinfunction "RD-1_2") (pintype "input"))
      (node (ref "U3") (pin "12") (pinfunction "TPIN-_12") (pintype "input"))
    )
    (net (code "92") (name "TPOUT+") (class "Default")
      (node (ref "R10") (pin "1") (pinfunction "1_1") (pintype "passive"))
      (node (ref "R12") (pin "1") (pinfunction "1_1") (pintype "passive"))
      (node (ref "U$6") (pin "C") (pinfunction "2_C") (pintype "bidirectional"))
      (node (ref "U2") (pin "5") (pinfunction "TD+1_5") (pintype "input"))
      (node (ref "U3") (pin "17") (pinfunction "TPOUT+_17") (pintype "output"))
    )
    (net (code "93") (name "TPOUT-") (class "Default")
      (node (ref "R17") (pin "1") (pinfunction "1_1") (pintype "passive"))
      (node (ref "R23") (pin "1") (pinfunction "1_1") (pintype "passive"))
      (node (ref "U$6") (pin "A") (pinfunction "1_A") (pintype "bidirectional"))
      (node (ref "U2") (pin "6") (pinfunction "TD-1_6") (pintype "input"))
      (node (ref "U3") (pin "16") (pinfunction "TPOUT-_16") (pintype "output"))
    )
    (net (code "94") (name "TXL") (class "Default")
      (node (ref "IC7") (pin "22") (pinfunction "RXLED_22") (pintype "input"))
      (node (ref "TX") (pin "C") (pinfunction "C_C") (pintype "passive"))
    )
    (net (code "95") (name "TX_FTDI") (class "Default")
      (node (ref "IC2") (pin "3") (pinfunction "(TXD0)PE1_3") (pintype "bidirectional"))
      (node (ref "IC7") (pin "5") (pinfunction "RXD_5") (pintype "input"))
    )
    (net (code "96") (name "TX_MAX") (class "Default")
      (node (ref "IC2") (pin "46") (pinfunction "(TXD1/INT3)PD3_46") (pintype "bidirectional"))
      (node (ref "IC8") (pin "4") (pinfunction "D_4") (pintype "input"))
      (node (ref "R9") (pin "2") (pinfunction "2_2") (pintype "passive"))
    )
    (net (code "97") (name "VCC") (class "Default")
      (node (ref "C1") (pin "1") (pinfunction "1_1") (pintype "passive"))
      (node (ref "C11") (pin "+") (pinfunction "+_+") (pintype "passive"))
      (node (ref "C12") (pin "1") (pinfunction "1_1") (pintype "passive"))
      (node (ref "C15") (pin "1") (pinfunction "1_1") (pintype "passive"))
      (node (ref "C2") (pin "1") (pinfunction "1_1") (pintype "passive"))
      (node (ref "C20") (pin "1") (pinfunction "1_1") (pintype "passive"))
      (node (ref "C3") (pin "1") (pinfunction "1_1") (pintype "passive"))
      (node (ref "C4") (pin "1") (pinfunction "1_1") (pintype "passive"))
      (node (ref "D2") (pin "C") (pinfunction "C_C") (pintype "passive"))
      (node (ref "DC2DC_1") (pin "3") (pinfunction "+5V_3") (pintype "power_in"))
      (node (ref "F1") (pin "1") (pinfunction "1_1") (pintype "passive"))
      (node (ref "IC2") (pin "10") (pinfunction "VCC_10") (pintype "power_in"))
      (node (ref "IC2") (pin "100") (pinfunction "AVCC_100") (pintype "power_in"))
      (node (ref "IC2") (pin "31") (pinfunction "VCC1_31") (pintype "power_in"))
      (node (ref "IC2") (pin "61") (pinfunction "VCC2_61") (pintype "power_in"))
      (node (ref "IC2") (pin "80") (pinfunction "VCC3_80") (pintype "power_in"))
      (node (ref "IC3") (pin "14") (pinfunction "VCC_14") (pintype "power_in"))
      (node (ref "IC7") (pin "19") (pinfunction "RESET_19") (pintype "input"))
      (node (ref "IC7") (pin "20") (pinfunction "VCC_20") (pintype "power_in"))
      (node (ref "IC7") (pin "4") (pinfunction "VCCIO_4") (pintype "power_in"))
      (node (ref "L2") (pin "2") (pinfunction "2_2") (pintype "passive"))
      (node (ref "LED1") (pin "A") (pinfunction "A_A") (pintype "passive"))
      (node (ref "LED2") (pin "A") (pinfunction "A_A") (pintype "passive"))
      (node (ref "R21") (pin "2") (pinfunction "2_2") (pintype "passive"))
      (node (ref "R22") (pin "2") (pinfunction "2_2") (pintype "passive"))
      (node (ref "R25") (pin "2") (pinfunction "2_2") (pintype "passive"))
      (node (ref "R28") (pin "1") (pinfunction "1_1") (pintype "passive"))
      (node (ref "R3") (pin "2") (pinfunction "2_2") (pintype "passive"))
      (node (ref "R30") (pin "1") (pinfunction "1_1") (pintype "passive"))
      (node (ref "R33") (pin "1") (pinfunction "1_1") (pintype "passive"))
      (node (ref "R44") (pin "2") (pinfunction "2_2") (pintype "passive"))
      (node (ref "R45") (pin "2") (pinfunction "2_2") (pintype "passive"))
      (node (ref "R46") (pin "2") (pinfunction "2_2") (pintype "passive"))
      (node (ref "R47") (pin "2") (pinfunction "2_2") (pintype "passive"))
      (node (ref "SW1") (pin "7") (pinfunction "7_7") (pintype "passive"))
      (node (ref "U1") (pin "1") (pinfunction "IN_1") (pintype "input"))
    )
    (net (code "98") (name "VDD_IC") (class "Default")
      (node (ref "C16") (pin "1") (pinfunction "1_1") (pintype "passive"))
      (node (ref "L2") (pin "1") (pinfunction "1_1") (pintype "passive"))
      (node (ref "U$1") (pin "8") (pinfunction "VDD_8") (pintype "output"))
    )
    (net (code "99") (name "VMOT") (class "Default")
      (node (ref "U$2") (pin "VS+") (pinfunction "VMOT_VS+") (pintype "power_in"))
      (node (ref "U$5") (pin "P$6") (pinfunction "P$6_P$6") (pintype "bidirectional"))
    )
    (net (code "100") (name "XTAL1") (class "Default")
      (node (ref "IC2") (pin "34") (pinfunction "XTAL1_34") (pintype "input"))
      (node (ref "R20") (pin "1") (pinfunction "1_1") (pintype "passive"))
      (node (ref "Y1") (pin "3") (pinfunction "3_3") (pintype "passive"))
    )
    (net (code "101") (name "XVCC") (class "Default")
      (node (ref "F1") (pin "2") (pinfunction "2_2") (pintype "passive"))
      (node (ref "USB") (pin "VBUS") (pinfunction "VBUS_VBUS") (pintype "bidirectional"))
    )
    (net (code "102") (name "unconnected-(IC2-(A8)PC0-Pad53)") (class "Default")
      (node (ref "IC2") (pin "53") (pinfunction "(A8)PC0_53") (pintype "bidirectional"))
    )
    (net (code "103") (name "unconnected-(IC2-(A9)PC1-Pad54)") (class "Default")
      (node (ref "IC2") (pin "54") (pinfunction "(A9)PC1_54") (pintype "bidirectional"))
    )
    (net (code "104") (name "unconnected-(IC2-(A10)PC2-Pad55)") (class "Default")
      (node (ref "IC2") (pin "55") (pinfunction "(A10)PC2_55") (pintype "bidirectional"))
    )
    (net (code "105") (name "unconnected-(IC2-(A15)PC7-Pad60)") (class "Default")
      (node (ref "IC2") (pin "60") (pinfunction "(A15)PC7_60") (pintype "bidirectional"))
    )
    (net (code "106") (name "unconnected-(IC2-(AD0)PA0-Pad78)") (class "Default")
      (node (ref "IC2") (pin "78") (pinfunction "(AD0)PA0_78") (pintype "bidirectional"))
    )
    (net (code "107") (name "unconnected-(IC2-(AD1)PA1-Pad77)") (class "Default")
      (node (ref "IC2") (pin "77") (pinfunction "(AD1)PA1_77") (pintype "bidirectional"))
    )
    (net (code "108") (name "unconnected-(IC2-(AD2)PA2-Pad76)") (class "Default")
      (node (ref "IC2") (pin "76") (pinfunction "(AD2)PA2_76") (pintype "bidirectional"))
    )
    (net (code "109") (name "unconnected-(IC2-(AD3)PA3-Pad75)") (class "Default")
      (node (ref "IC2") (pin "75") (pinfunction "(AD3)PA3_75") (pintype "bidirectional"))
    )
    (net (code "110") (name "unconnected-(IC2-(AD4)PA4-Pad74)") (class "Default")
      (node (ref "IC2") (pin "74") (pinfunction "(AD4)PA4_74") (pintype "bidirectional"))
    )
    (net (code "111") (name "unconnected-(IC2-(AD5)PA5-Pad73)") (class "Default")
      (node (ref "IC2") (pin "73") (pinfunction "(AD5)PA5_73") (pintype "bidirectional"))
    )
    (net (code "112") (name "unconnected-(IC2-(AD6)PA6-Pad72)") (class "Default")
      (node (ref "IC2") (pin "72") (pinfunction "(AD6)PA6_72") (pintype "bidirectional"))
    )
    (net (code "113") (name "unconnected-(IC2-(AD7)PA7-Pad71)") (class "Default")
      (node (ref "IC2") (pin "71") (pinfunction "(AD7)PA7_71") (pintype "bidirectional"))
    )
    (net (code "114") (name "unconnected-(IC2-(ADC0)PF0-Pad97)") (class "Default")
      (node (ref "IC2") (pin "97") (pinfunction "(ADC0)PF0_97") (pintype "bidirectional"))
    )
    (net (code "115") (name "unconnected-(IC2-(ADC1)PF1-Pad96)") (class "Default")
      (node (ref "IC2") (pin "96") (pinfunction "(ADC1)PF1_96") (pintype "bidirectional"))
    )
    (net (code "116") (name "unconnected-(IC2-(ADC2)PF2-Pad95)") (class "Default")
      (node (ref "IC2") (pin "95") (pinfunction "(ADC2)PF2_95") (pintype "bidirectional"))
    )
    (net (code "117") (name "unconnected-(IC2-(ADC3)PF3-Pad94)") (class "Default")
      (node (ref "IC2") (pin "94") (pinfunction "(ADC3)PF3_94") (pintype "bidirectional"))
    )
    (net (code "118") (name "unconnected-(IC2-(ADC4{slash}TCK)PF4-Pad93)") (class "Default")
      (node (ref "IC2") (pin "93") (pinfunction "(ADC4/TCK)PF4_93") (pintype "bidirectional"))
    )
    (net (code "119") (name "unconnected-(IC2-(ADC5{slash}TMS)PF5-Pad92)") (class "Default")
      (node (ref "IC2") (pin "92") (pinfunction "(ADC5/TMS)PF5_92") (pintype "bidirectional"))
    )
    (net (code "120") (name "unconnected-(IC2-(ADC6{slash}TDO)PF6-Pad91)") (class "Default")
      (node (ref "IC2") (pin "91") (pinfunction "(ADC6/TDO)PF6_91") (pintype "bidirectional"))
    )
    (net (code "121") (name "unconnected-(IC2-(ADC7{slash}TDI)PF7-Pad90)") (class "Default")
      (node (ref "IC2") (pin "90") (pinfunction "(ADC7/TDI)PF7_90") (pintype "bidirectional"))
    )
    (net (code "122") (name "unconnected-(IC2-(ALE)PG2-Pad70)") (class "Default")
      (node (ref "IC2") (pin "70") (pinfunction "(ALE)PG2_70") (pintype "bidirectional"))
    )
    (net (code "123") (name "unconnected-(IC2-(CLKO{slash}ICP3{slash}INT7)PE7-Pad9)") (class "Default")
      (node (ref "IC2") (pin "9") (pinfunction "(CLKO/ICP3/INT7)PE7_9") (pintype "bidirectional"))
    )
    (net (code "124") (name "unconnected-(IC2-(ICP1)PD4-Pad47)") (class "Default")
      (node (ref "IC2") (pin "47") (pinfunction "(ICP1)PD4_47") (pintype "bidirectional"))
    )
    (net (code "125") (name "unconnected-(IC2-(OC0A{slash}OC1C{slash}PCINT7)PB7-Pad26)") (class "Default")
      (node (ref "IC2") (pin "26") (pinfunction "(OC0A/OC1C/PCINT7)PB7_26") (pintype "bidirectional"))
    )
    (net (code "126") (name "unconnected-(IC2-(OC0B)PG5-Pad1)") (class "Default")
      (node (ref "IC2") (pin "1") (pinfunction "(OC0B)PG5_1") (pintype "bidirectional"))
    )
    (net (code "127") (name "unconnected-(IC2-(OC1A{slash}PCINT5)PB5-Pad24)") (class "Default")
      (node (ref "IC2") (pin "24") (pinfunction "(OC1A/PCINT5)PB5_24") (pintype "bidirectional"))
    )
    (net (code "128") (name "unconnected-(IC2-(OC1B{slash}PCINT6)PB6-Pad25)") (class "Default")
      (node (ref "IC2") (pin "25") (pinfunction "(OC1B/PCINT6)PB6_25") (pintype "bidirectional"))
    )
    (net (code "129") (name "unconnected-(IC2-(OC3B{slash}INT4)PE4-Pad6)") (class "Default")
      (node (ref "IC2") (pin "6") (pinfunction "(OC3B/INT4)PE4_6") (pintype "bidirectional"))
    )
    (net (code "130") (name "unconnected-(IC2-(RD)PG1-Pad52)") (class "Default")
      (node (ref "IC2") (pin "52") (pinfunction "(RD)PG1_52") (pintype "bidirectional"))
    )
    (net (code "131") (name "unconnected-(IC2-(T1)PD6-Pad49)") (class "Default")
      (node (ref "IC2") (pin "49") (pinfunction "(T1)PD6_49") (pintype "bidirectional"))
    )
    (net (code "132") (name "unconnected-(IC2-(T3{slash}INT6)PE6-Pad8)") (class "Default")
      (node (ref "IC2") (pin "8") (pinfunction "(T3/INT6)PE6_8") (pintype "bidirectional"))
    )
    (net (code "133") (name "unconnected-(IC2-(TOSC1)PG4-Pad29)") (class "Default")
      (node (ref "IC2") (pin "29") (pinfunction "(TOSC1)PG4_29") (pintype "bidirectional"))
    )
    (net (code "134") (name "unconnected-(IC2-(TOSC2)PG3-Pad28)") (class "Default")
      (node (ref "IC2") (pin "28") (pinfunction "(TOSC2)PG3_28") (pintype "bidirectional"))
    )
    (net (code "135") (name "unconnected-(IC2-(WR)PG0-Pad51)") (class "Default")
      (node (ref "IC2") (pin "51") (pinfunction "(WR)PG0_51") (pintype "bidirectional"))
    )
    (net (code "136") (name "unconnected-(IC2-(XCK0{slash}AIN0)PE2-Pad4)") (class "Default")
      (node (ref "IC2") (pin "4") (pinfunction "(XCK0/AIN0)PE2_4") (pintype "bidirectional"))
    )
    (net (code "137") (name "unconnected-(IC2-(XCK1)PD5-Pad48)") (class "Default")
      (node (ref "IC2") (pin "48") (pinfunction "(XCK1)PD5_48") (pintype "bidirectional"))
    )
    (net (code "138") (name "unconnected-(IC2-AREF-Pad98)") (class "Default")
      (node (ref "IC2") (pin "98") (pinfunction "AREF_98") (pintype "bidirectional"))
    )
    (net (code "139") (name "unconnected-(IC2-PH0(RXD2)-Pad12)") (class "Default")
      (node (ref "IC2") (pin "12") (pinfunction "PH0(RXD2)_12") (pintype "bidirectional"))
    )
    (net (code "140") (name "unconnected-(IC2-PH1(TXD2)-Pad13)") (class "Default")
      (node (ref "IC2") (pin "13") (pinfunction "PH1(TXD2)_13") (pintype "bidirectional"))
    )
    (net (code "141") (name "unconnected-(IC2-PH2(XCK2)-Pad14)") (class "Default")
      (node (ref "IC2") (pin "14") (pinfunction "PH2(XCK2)_14") (pintype "bidirectional"))
    )
    (net (code "142") (name "unconnected-(IC2-PH3(OC4A)-Pad15)") (class "Default")
      (node (ref "IC2") (pin "15") (pinfunction "PH3(OC4A)_15") (pintype "bidirectional"))
    )
    (net (code "143") (name "unconnected-(IC2-PH4(OC4B)-Pad16)") (class "Default")
      (node (ref "IC2") (pin "16") (pinfunction "PH4(OC4B)_16") (pintype "bidirectional"))
    )
    (net (code "144") (name "unconnected-(IC2-PH5(OC4C)-Pad17)") (class "Default")
      (node (ref "IC2") (pin "17") (pinfunction "PH5(OC4C)_17") (pintype "bidirectional"))
    )
    (net (code "145") (name "unconnected-(IC2-PH7(T4)-Pad27)") (class "Default")
      (node (ref "IC2") (pin "27") (pinfunction "PH7(T4)_27") (pintype "bidirectional"))
    )
    (net (code "146") (name "unconnected-(IC2-PJ1(TXD3{slash}PCINT10)-Pad64)") (class "Default")
      (node (ref "IC2") (pin "64") (pinfunction "PJ1(TXD3/PCINT10)_64") (pintype "bidirectional"))
    )
    (net (code "147") (name "unconnected-(IC2-PJ2(XCK3{slash}PCINT11)-Pad65)") (class "Default")
      (node (ref "IC2") (pin "65") (pinfunction "PJ2(XCK3/PCINT11)_65") (pintype "bidirectional"))
    )
    (net (code "148") (name "unconnected-(IC2-PJ3(PCINT12)-Pad66)") (class "Default")
      (node (ref "IC2") (pin "66") (pinfunction "PJ3(PCINT12)_66") (pintype "bidirectional"))
    )
    (net (code "149") (name "unconnected-(IC2-PJ4(PCINT13)-Pad67)") (class "Default")
      (node (ref "IC2") (pin "67") (pinfunction "PJ4(PCINT13)_67") (pintype "bidirectional"))
    )
    (net (code "150") (name "unconnected-(IC2-PJ5(PCINT14)-Pad68)") (class "Default")
      (node (ref "IC2") (pin "68") (pinfunction "PJ5(PCINT14)_68") (pintype "bidirectional"))
    )
    (net (code "151") (name "unconnected-(IC2-PJ6(PCINT15)-Pad69)") (class "Default")
      (node (ref "IC2") (pin "69") (pinfunction "PJ6(PCINT15)_69") (pintype "bidirectional"))
    )
    (net (code "152") (name "unconnected-(IC2-PJ7-Pad79)") (class "Default")
      (node (ref "IC2") (pin "79") (pinfunction "PJ7_79") (pintype "bidirectional"))
    )
    (net (code "153") (name "unconnected-(IC2-PK0(ADC8{slash}PCINT16)-Pad89)") (class "Default")
      (node (ref "IC2") (pin "89") (pinfunction "PK0(ADC8/PCINT16)_89") (pintype "bidirectional"))
    )
    (net (code "154") (name "unconnected-(IC2-PK1(ADC9{slash}PCINT17)-Pad88)") (class "Default")
      (node (ref "IC2") (pin "88") (pinfunction "PK1(ADC9/PCINT17)_88") (pintype "bidirectional"))
    )
    (net (code "155") (name "unconnected-(IC2-PK2(ADC10{slash}PCINT18)-Pad87)") (class "Default")
      (node (ref "IC2") (pin "87") (pinfunction "PK2(ADC10/PCINT18)_87") (pintype "bidirectional"))
    )
    (net (code "156") (name "unconnected-(IC2-PK3(ADC11{slash}PCINT19)-Pad86)") (class "Default")
      (node (ref "IC2") (pin "86") (pinfunction "PK3(ADC11/PCINT19)_86") (pintype "bidirectional"))
    )
    (net (code "157") (name "unconnected-(IC2-PK4(ADC12{slash}PCINT20)-Pad85)") (class "Default")
      (node (ref "IC2") (pin "85") (pinfunction "PK4(ADC12/PCINT20)_85") (pintype "bidirectional"))
    )
    (net (code "158") (name "unconnected-(IC2-PK5(ADC13{slash}PCINT21)-Pad84)") (class "Default")
      (node (ref "IC2") (pin "84") (pinfunction "PK5(ADC13/PCINT21)_84") (pintype "bidirectional"))
    )
    (net (code "159") (name "unconnected-(IC2-PK6(ADC14{slash}PCINT22)-Pad83)") (class "Default")
      (node (ref "IC2") (pin "83") (pinfunction "PK6(ADC14/PCINT22)_83") (pintype "bidirectional"))
    )
    (net (code "160") (name "unconnected-(IC2-PK7(ADC15{slash}PCINT23)-Pad82)") (class "Default")
      (node (ref "IC2") (pin "82") (pinfunction "PK7(ADC15/PCINT23)_82") (pintype "bidirectional"))
    )
    (net (code "161") (name "unconnected-(IC2-PL4(OC5B)-Pad39)") (class "Default")
      (node (ref "IC2") (pin "39") (pinfunction "PL4(OC5B)_39") (pintype "bidirectional"))
    )
    (net (code "162") (name "unconnected-(IC2-PL5(OC5C)-Pad40)") (class "Default")
      (node (ref "IC2") (pin "40") (pinfunction "PL5(OC5C)_40") (pintype "bidirectional"))
    )
    (net (code "163") (name "unconnected-(IC2-PL6-Pad41)") (class "Default")
      (node (ref "IC2") (pin "41") (pinfunction "PL6_41") (pintype "bidirectional"))
    )
    (net (code "164") (name "unconnected-(IC2-PL7-Pad42)") (class "Default")
      (node (ref "IC2") (pin "42") (pinfunction "PL7_42") (pintype "bidirectional"))
    )
    (net (code "165") (name "unconnected-(IC7-CTS-Pad11)") (class "Default")
      (node (ref "IC7") (pin "11") (pinfunction "CTS_11") (pintype "input"))
    )
    (net (code "166") (name "unconnected-(IC7-DCD-Pad10)") (class "Default")
      (node (ref "IC7") (pin "10") (pinfunction "DCD_10") (pintype "input"))
    )
    (net (code "167") (name "unconnected-(IC7-DSR-Pad9)") (class "Default")
      (node (ref "IC7") (pin "9") (pinfunction "DSR_9") (pintype "input"))
    )
    (net (code "168") (name "unconnected-(IC7-OSCI-Pad27)") (class "Default")
      (node (ref "IC7") (pin "27") (pinfunction "OSCI_27") (pintype "input"))
    )
    (net (code "169") (name "unconnected-(IC7-OSCO-Pad28)") (class "Default")
      (node (ref "IC7") (pin "28") (pinfunction "OSCO_28") (pintype "output"))
    )
    (net (code "170") (name "unconnected-(IC7-PWREN-Pad14)") (class "Default")
      (node (ref "IC7") (pin "14") (pinfunction "PWREN_14") (pintype "input"))
    )
    (net (code "171") (name "unconnected-(IC7-RI-Pad6)") (class "Default")
      (node (ref "IC7") (pin "6") (pinfunction "RI_6") (pintype "input"))
    )
    (net (code "172") (name "unconnected-(IC7-RTS-Pad3)") (class "Default")
      (node (ref "IC7") (pin "3") (pinfunction "RTS_3") (pintype "output"))
    )
    (net (code "173") (name "unconnected-(IC7-SLEEP-Pad12)") (class "Default")
      (node (ref "IC7") (pin "12") (pinfunction "SLEEP_12") (pintype "input"))
    )
    (net (code "174") (name "unconnected-(IC7-TXDEN-Pad13)") (class "Default")
      (node (ref "IC7") (pin "13") (pinfunction "TXDEN_13") (pintype "input"))
    )
    (net (code "175") (name "unconnected-(K1-PadO)") (class "Default")
      (node (ref "K1") (pin "O") (pinfunction "O_O") (pintype "passive"))
    )
    (net (code "176") (name "unconnected-(K2-PadO)") (class "Default")
      (node (ref "K2") (pin "O") (pinfunction "O_O") (pintype "passive"))
    )
    (net (code "177") (name "unconnected-(K3-PadO)") (class "Default")
      (node (ref "K3") (pin "O") (pinfunction "O_O") (pintype "passive"))
    )
    (net (code "178") (name "unconnected-(K6-PadO)") (class "Default")
      (node (ref "K6") (pin "O") (pinfunction "O_O") (pintype "passive"))
    )
    (net (code "179") (name "unconnected-(Q1-C{slash}-Pad2@1)") (class "Default")
      (node (ref "Q1") (pin "2@1") (pinfunction "C/_2@1") (pintype "passive"))
    )
    (net (code "180") (name "unconnected-(Q2-C{slash}-Pad2@1)") (class "Default")
      (node (ref "Q2") (pin "2@1") (pinfunction "C/_2@1") (pintype "passive"))
    )
    (net (code "181") (name "unconnected-(U$2-D0{slash}RX1-PadD0)") (class "Default")
      (node (ref "U$2") (pin "D0") (pinfunction "D0/RX1_D0") (pintype "bidirectional"))
    )
    (net (code "182") (name "unconnected-(U$2-D1{slash}TX0-PadD1)") (class "Default")
      (node (ref "U$2") (pin "D1") (pinfunction "D1/TX0_D1") (pintype "bidirectional"))
    )
    (net (code "183") (name "unconnected-(U$2-D2{slash}FLAG-PadD2-FLAG)") (class "Default")
      (node (ref "U$2") (pin "D2-FLAG") (pinfunction "D2/FLAG_D2-FLAG") (pintype "bidirectional"))
    )
    (net (code "184") (name "unconnected-(U$2-D4{slash}BUSY-PadD4-BUSY)") (class "Default")
      (node (ref "U$2") (pin "D4-BUSY") (pinfunction "D4/BUSY_D4-BUSY") (pintype "bidirectional"))
    )
    (net (code "185") (name "unconnected-(U$2-D9{slash}STCK-PadD9-STCK)") (class "Default")
      (node (ref "U$2") (pin "D9-STCK") (pinfunction "D9/STCK_D9-STCK") (pintype "bidirectional"))
    )
    (net (code "186") (name "unconnected-(U$2-PadA0)") (class "Default")
      (node (ref "U$2") (pin "A0") (pinfunction "A0_A0") (pintype "bidirectional"))
    )
    (net (code "187") (name "unconnected-(U$2-PadA1)") (class "Default")
      (node (ref "U$2") (pin "A1") (pinfunction "A1_A1") (pintype "bidirectional"))
    )
    (net (code "188") (name "unconnected-(U$2-PadA3)") (class "Default")
      (node (ref "U$2") (pin "A3") (pinfunction "A3_A3") (pintype "bidirectional"))
    )
    (net (code "189") (name "unconnected-(U$2-PadA4)") (class "Default")
      (node (ref "U$2") (pin "A4") (pinfunction "A4_A4") (pintype "bidirectional"))
    )
    (net (code "190") (name "unconnected-(U$2-PadA5)") (class "Default")
      (node (ref "U$2") (pin "A5") (pinfunction "A5_A5") (pintype "bidirectional"))
    )
    (net (code "191") (name "unconnected-(U$2-PadD3)") (class "Default")
      (node (ref "U$2") (pin "D3") (pinfunction "D3_D3") (pintype "bidirectional"))
    )
    (net (code "192") (name "unconnected-(U$2-PadD5)") (class "Default")
      (node (ref "U$2") (pin "D5") (pinfunction "D5_D5") (pintype "bidirectional"))
    )
    (net (code "193") (name "unconnected-(U$2-PadD6)") (class "Default")
      (node (ref "U$2") (pin "D6") (pinfunction "D6_D6") (pintype "bidirectional"))
    )
    (net (code "194") (name "unconnected-(U$2-PadD7)") (class "Default")
      (node (ref "U$2") (pin "D7") (pinfunction "D7_D7") (pintype "bidirectional"))
    )
    (net (code "195") (name "unconnected-(U$2-PadD10)") (class "Default")
      (node (ref "U$2") (pin "D10") (pinfunction "D10_D10") (pintype "bidirectional"))
    )
    (net (code "196") (name "unconnected-(U2-CR1-Pad3)") (class "Default")
      (node (ref "U2") (pin "3") (pinfunction "CR1_3") (pintype "input"))
    )
    (net (code "197") (name "unconnected-(U3-CLKOUT-Pad3)") (class "Default")
      (node (ref "U3") (pin "3") (pinfunction "CLKOUT_3") (pintype "output"))
    )
    (net (code "198") (name "unconnected-(U3-WOL-Pad5)") (class "Default")
      (node (ref "U3") (pin "5") (pinfunction "WOL_5") (pintype "output"))
    )
  )
)
